# MicroMouse_v02.net
KiCad netlist of a schematic drawn in EasyEDA Pro
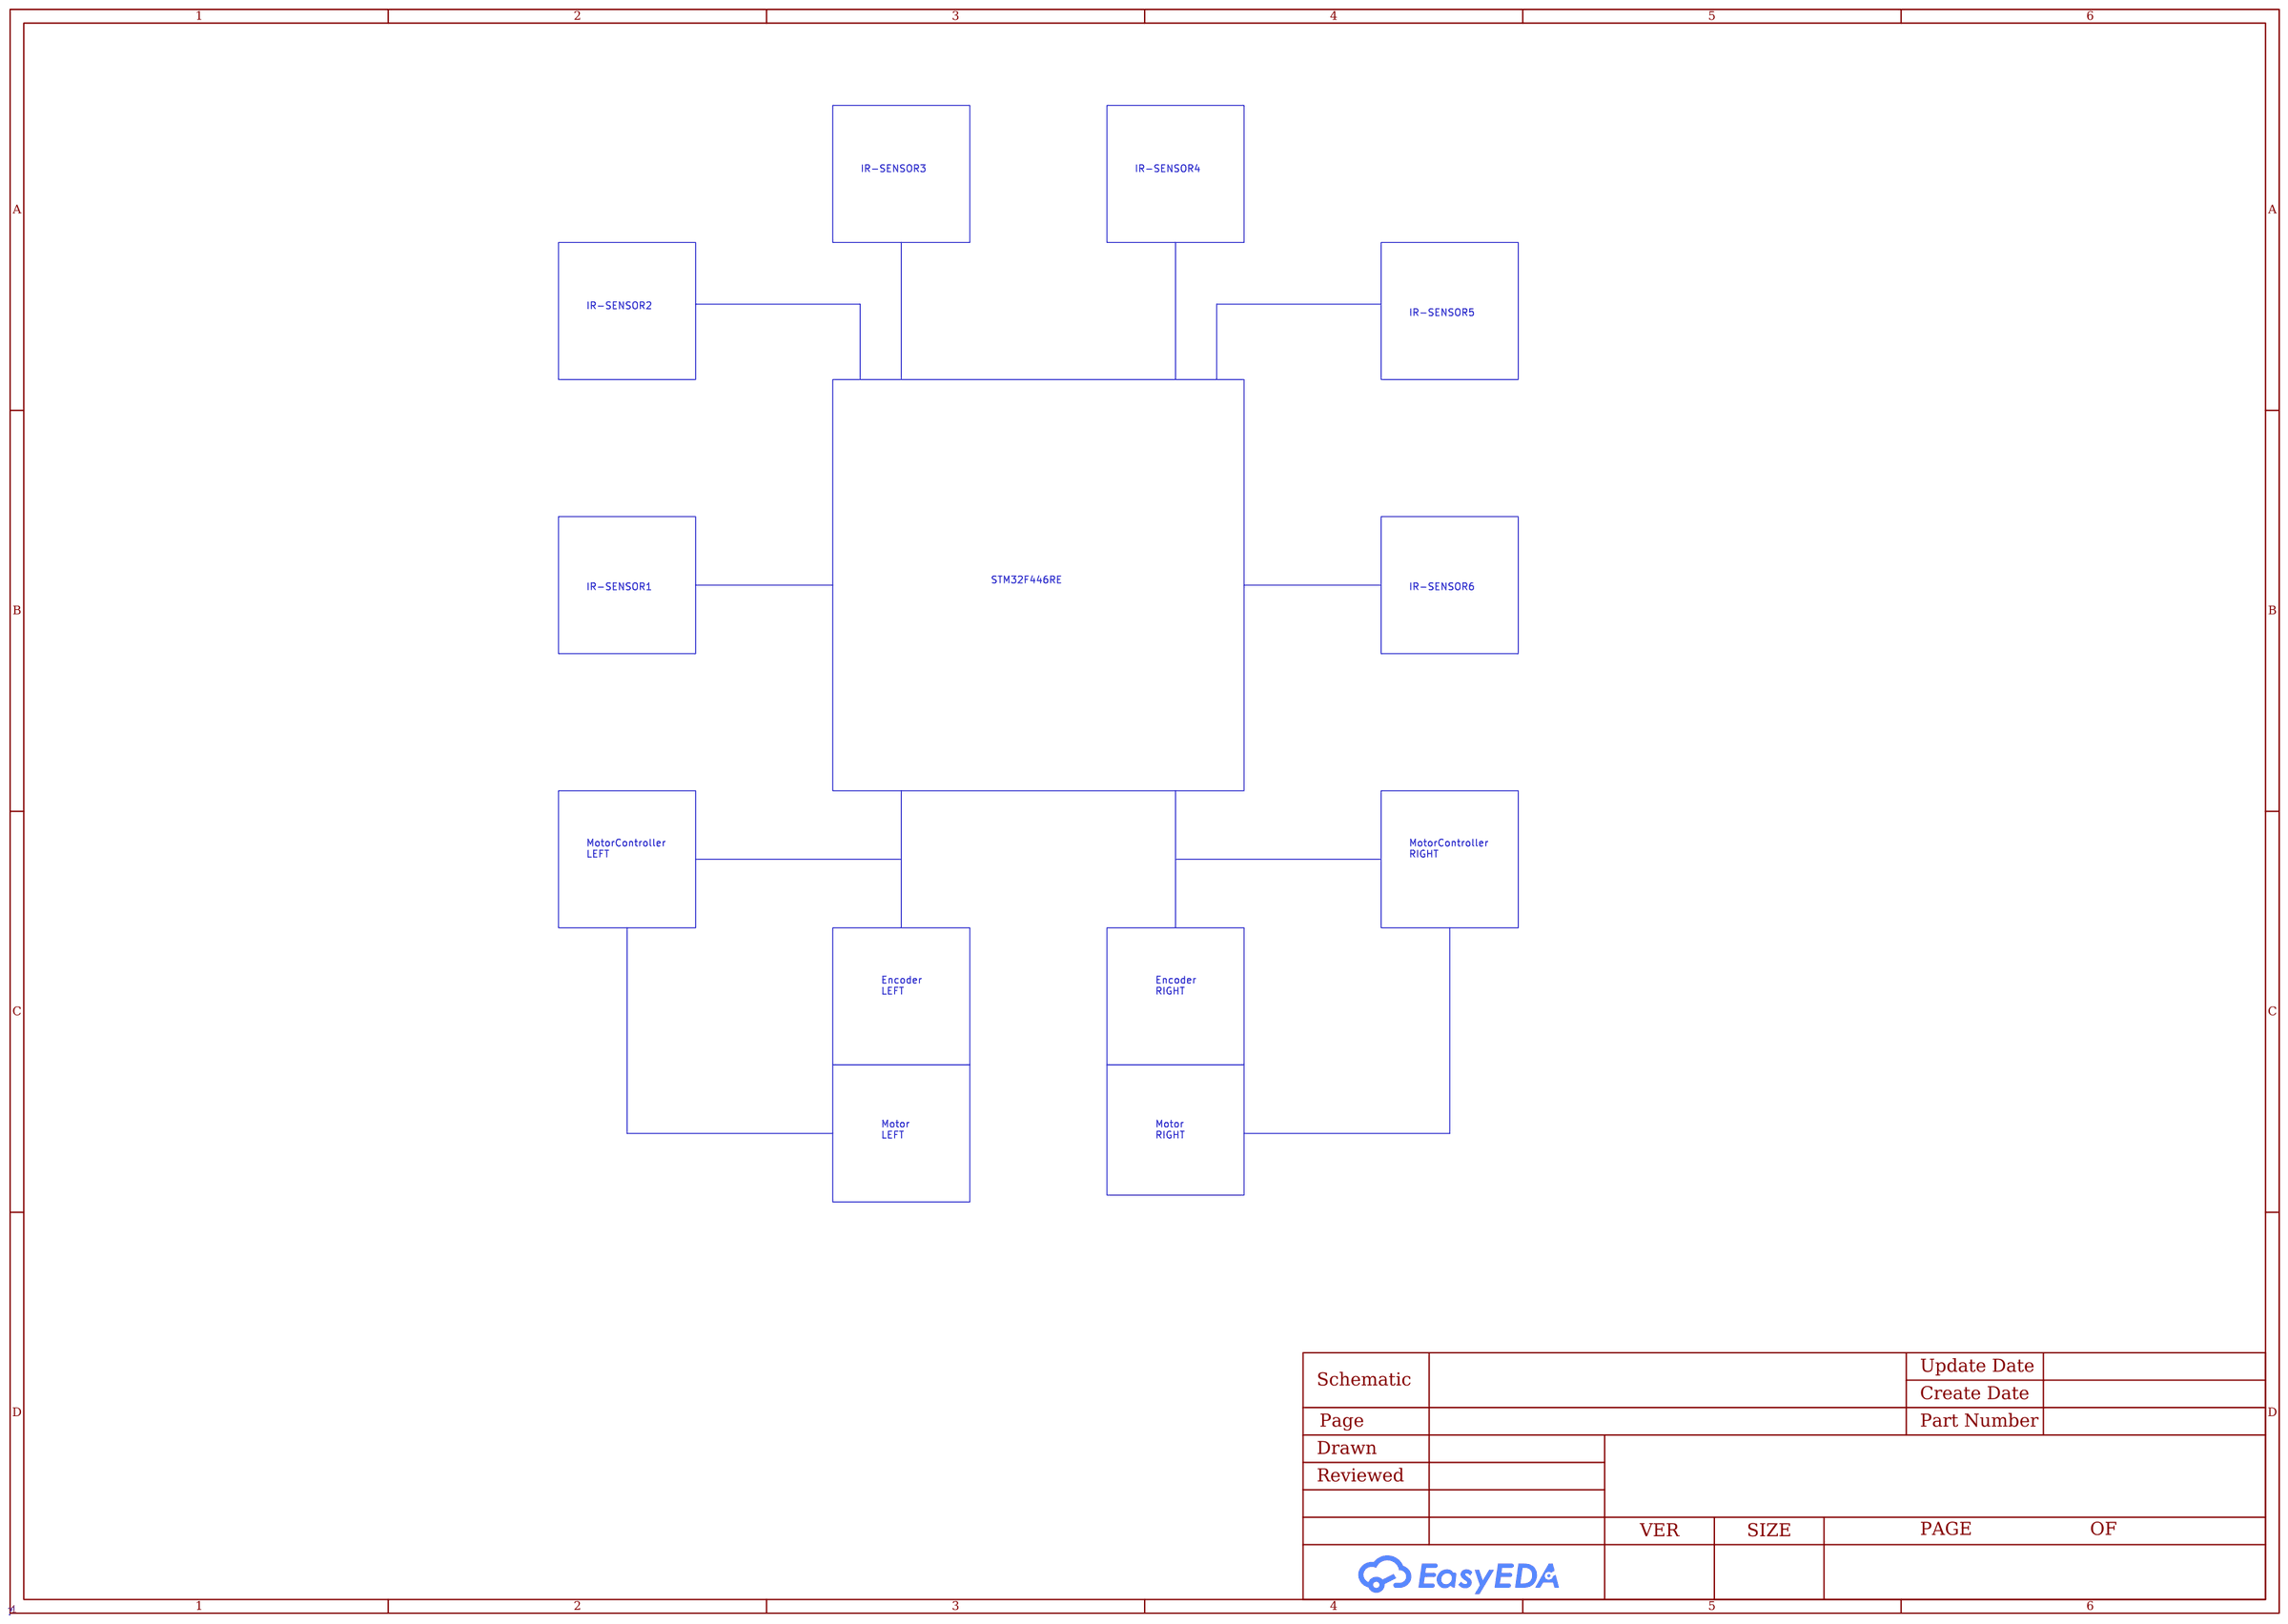
[diagram p0: Overview]
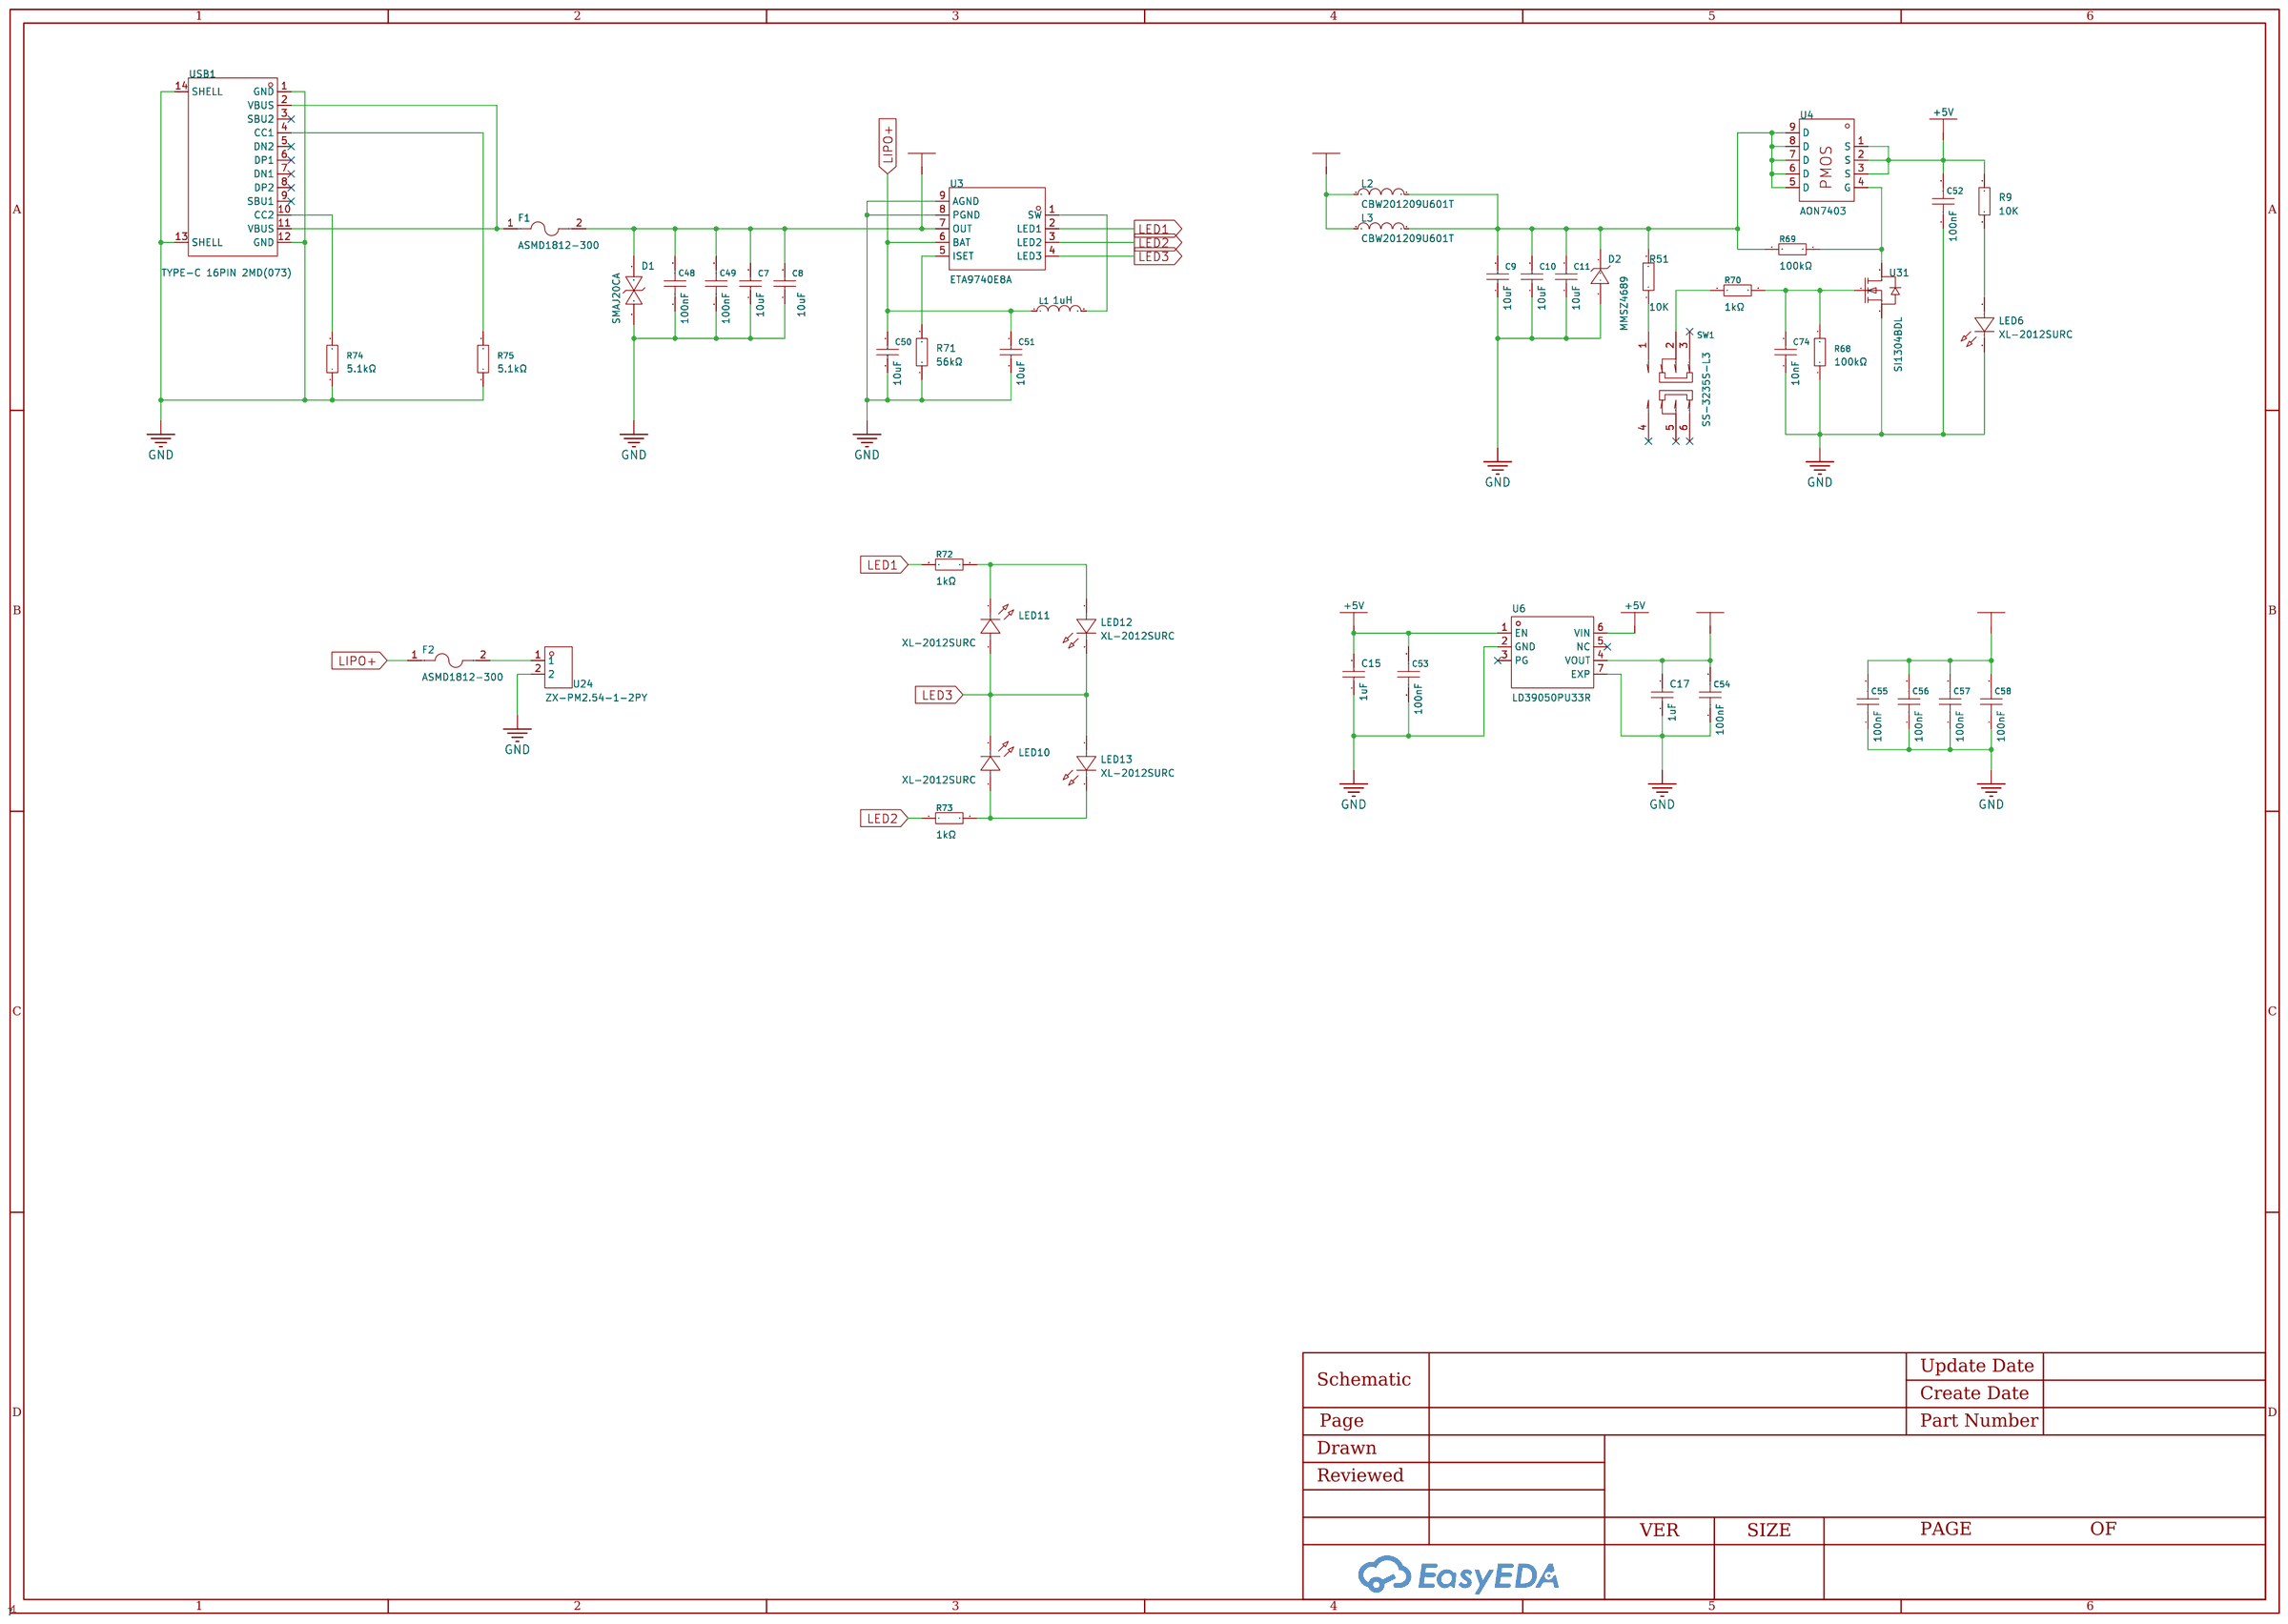
[diagram p1: VCC]
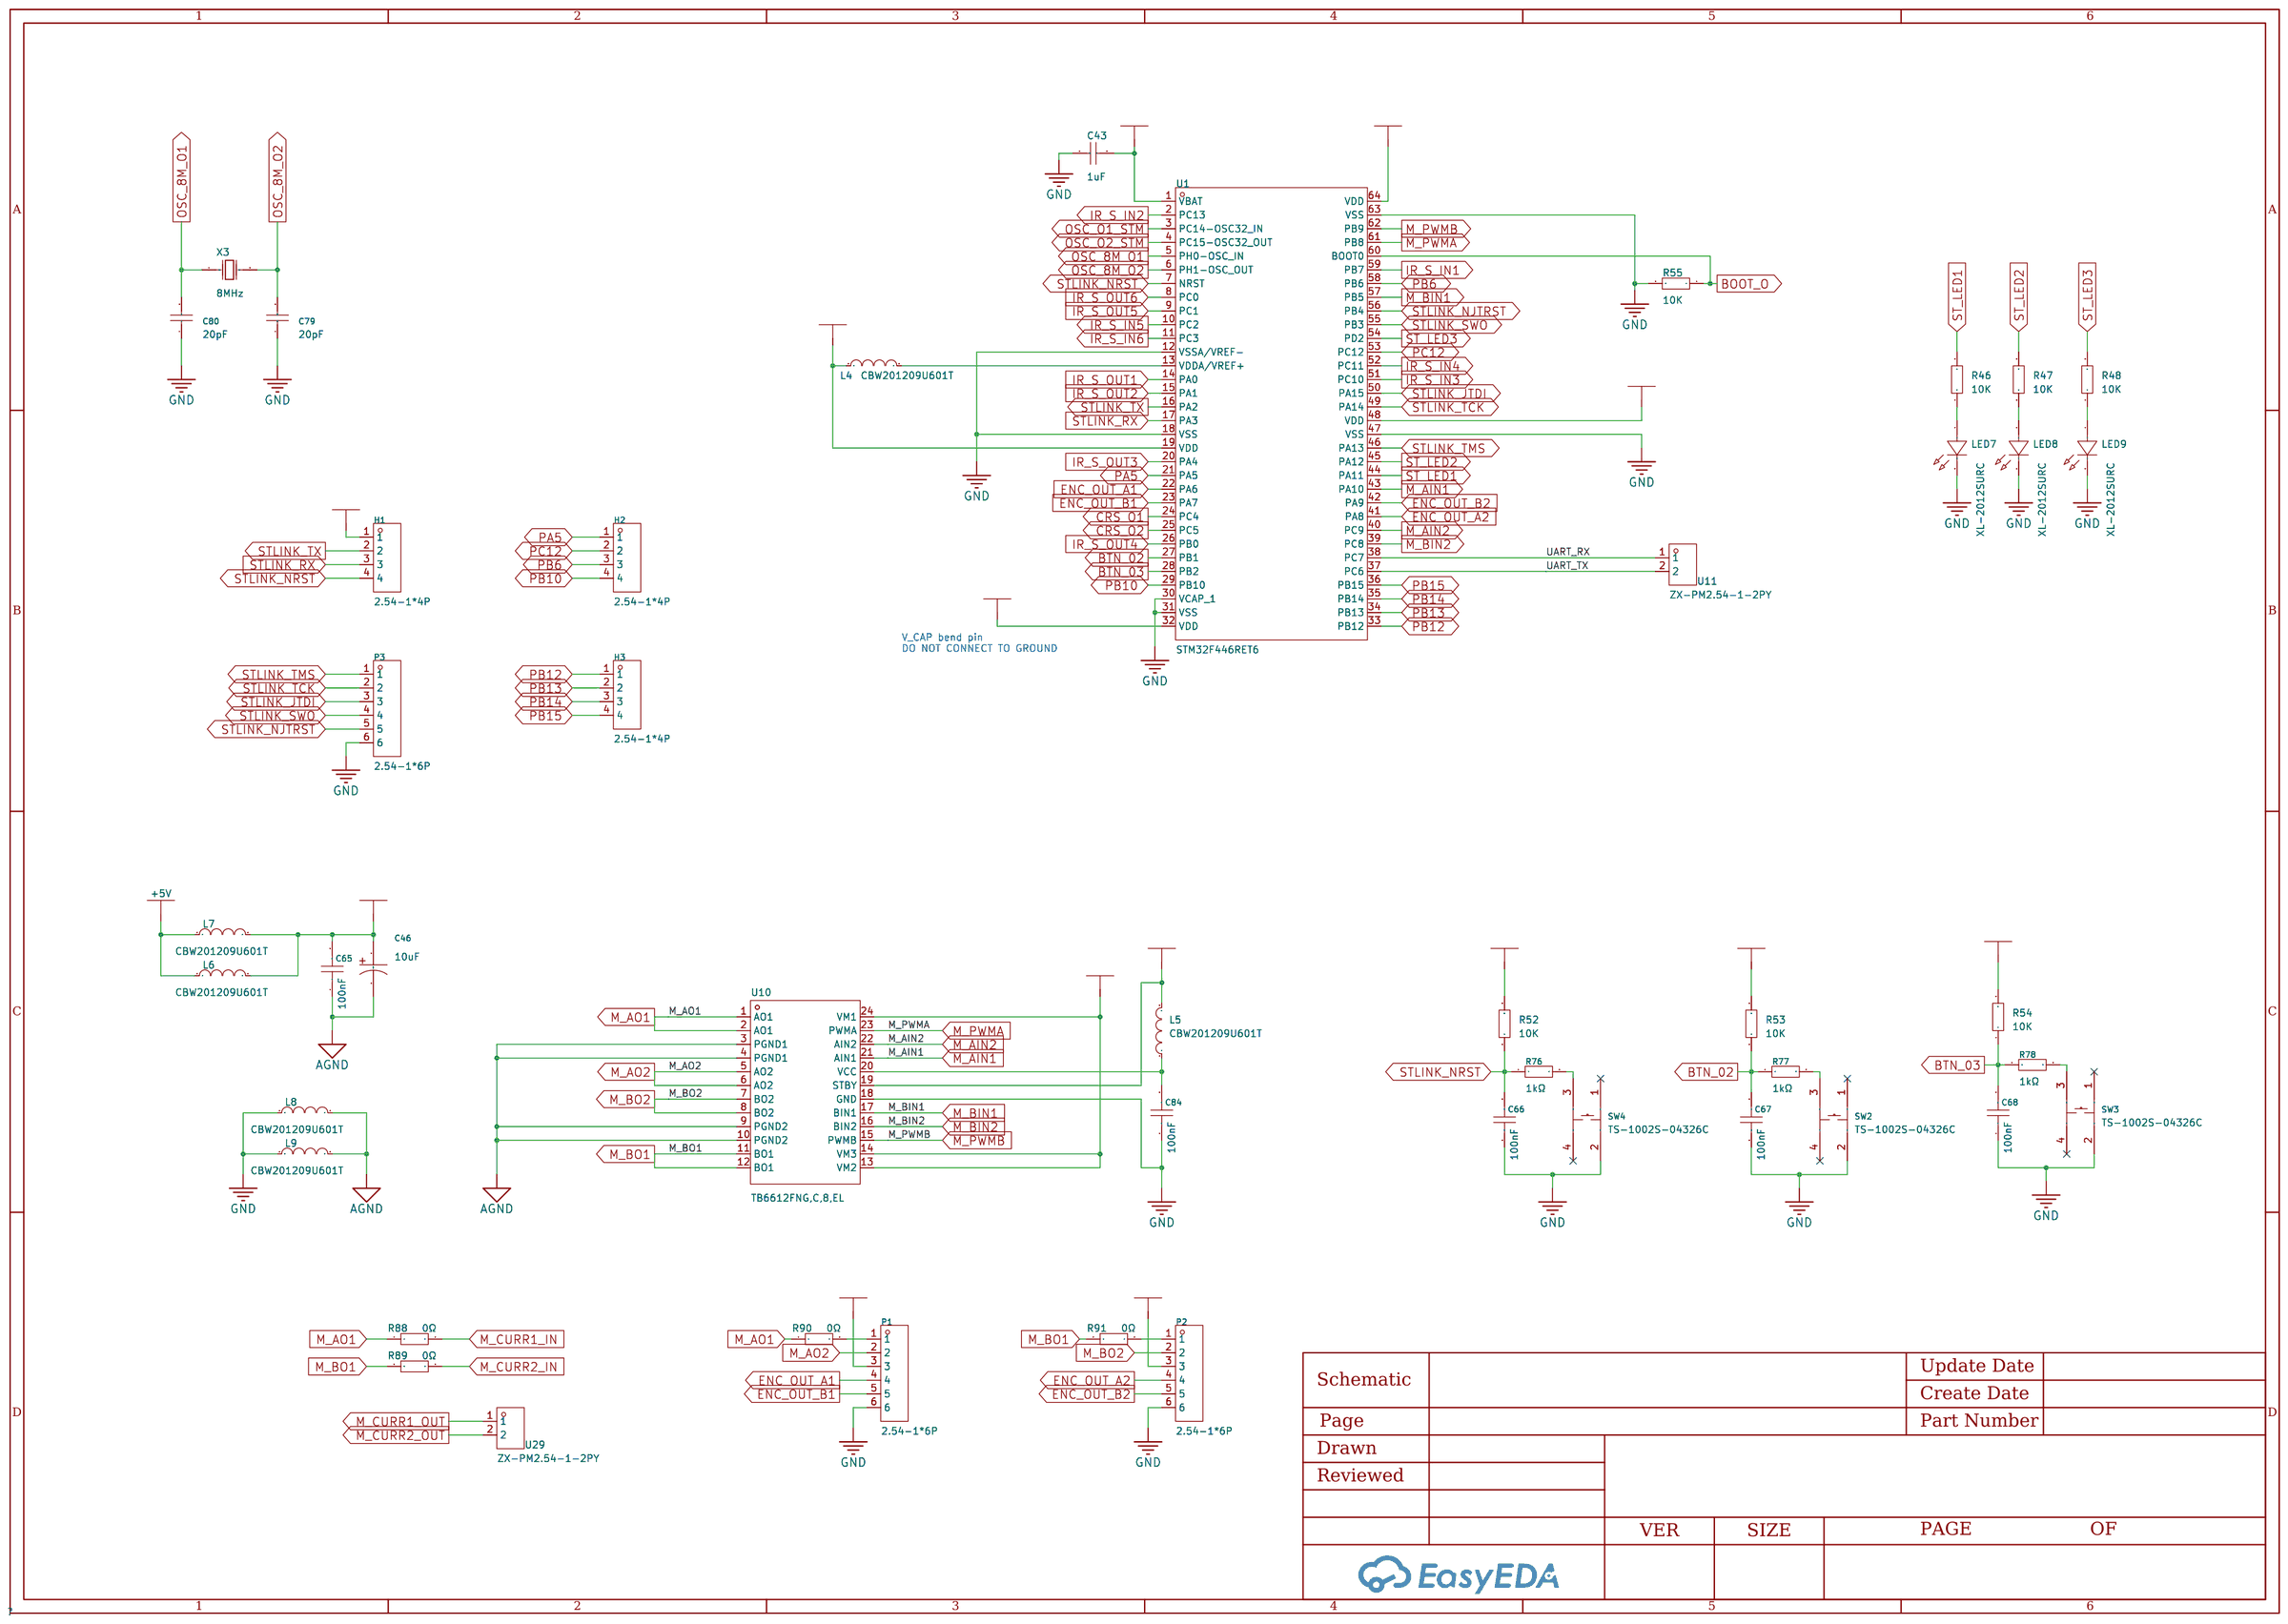
[diagram p2: Controller]
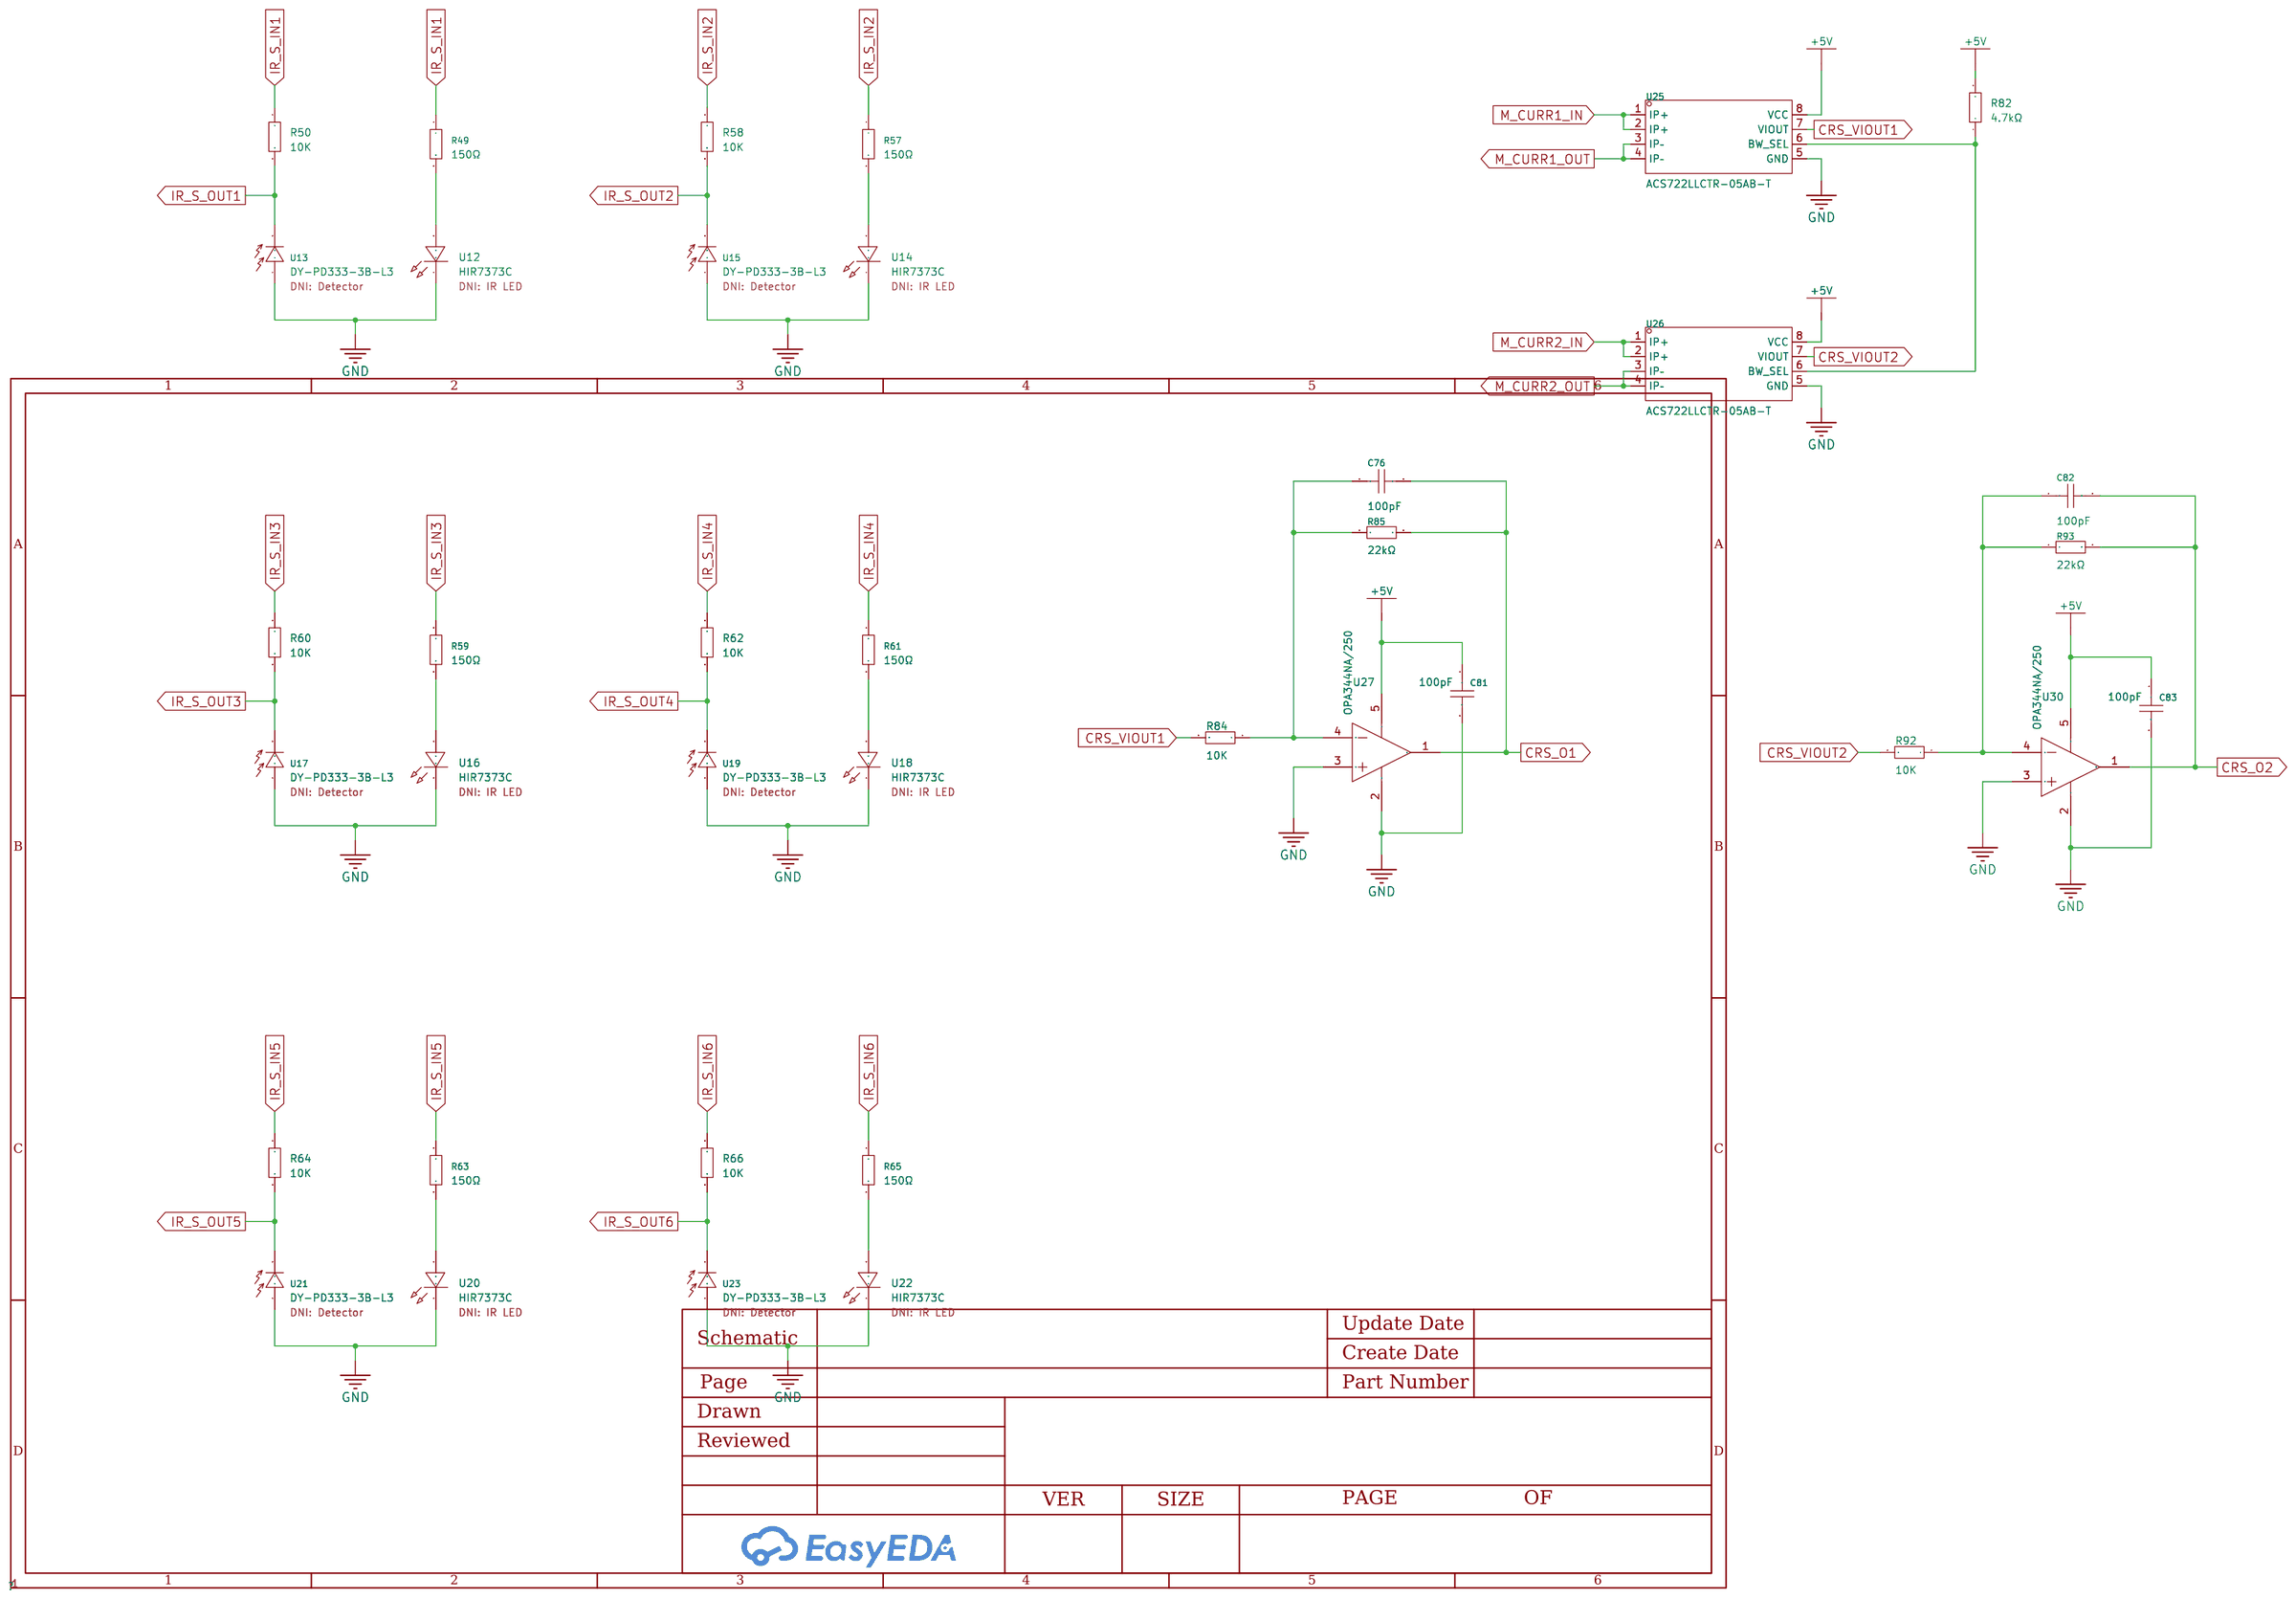
[diagram p3: Sensors]

(export (version "E")
  (design (tool "Eeschema 10.0.6"))
  (components
    (comp (ref "C7")
      (value "10uF")
      (footprint "easyedapro:C0805")
      (fields
        (field (name "Manufacturer Part") "CL21A106KPFNNNE")
        (field (name "Manufacturer") "SAMSUNG(三星)")
      )
      (libsource (lib "easyedapro") (part "CL21A106KPFNNNE"))
    )
    (comp (ref "C8")
      (value "10uF")
      (footprint "easyedapro:C0805")
      (fields
        (field (name "Manufacturer Part") "CL21A106KPFNNNE")
        (field (name "Manufacturer") "SAMSUNG(三星)")
      )
      (libsource (lib "easyedapro") (part "CL21A106KPFNNNE"))
    )
    (comp (ref "C9")
      (value "10uF")
      (footprint "easyedapro:C0805")
      (fields
        (field (name "Manufacturer Part") "CL21A106KPFNNNE")
        (field (name "Manufacturer") "SAMSUNG(三星)")
      )
      (libsource (lib "easyedapro") (part "CL21A106KPFNNNE"))
    )
    (comp (ref "C10")
      (value "10uF")
      (footprint "easyedapro:C0805")
      (fields
        (field (name "Manufacturer Part") "CL21A106KPFNNNE")
        (field (name "Manufacturer") "SAMSUNG(三星)")
      )
      (libsource (lib "easyedapro") (part "CL21A106KPFNNNE"))
    )
    (comp (ref "C11")
      (value "10uF")
      (footprint "easyedapro:C0805")
      (fields
        (field (name "Manufacturer Part") "CL21A106KPFNNNE")
        (field (name "Manufacturer") "SAMSUNG(三星)")
      )
      (libsource (lib "easyedapro") (part "CL21A106KPFNNNE"))
    )
    (comp (ref "C15")
      (value "1uF")
      (footprint "easyedapro:C0603")
      (fields
        (field (name "Manufacturer Part") "CL10A105KO8NNNC")
        (field (name "Manufacturer") "SAMSUNG(三星)")
      )
      (libsource (lib "easyedapro") (part "CL10A105KO8NNNC"))
    )
    (comp (ref "C17")
      (value "1uF")
      (footprint "easyedapro:C0603")
      (fields
        (field (name "Manufacturer Part") "CL10A105KO8NNNC")
        (field (name "Manufacturer") "SAMSUNG(三星)")
      )
      (libsource (lib "easyedapro") (part "CL10A105KO8NNNC"))
    )
    (comp (ref "C48")
      (value "100nF")
      (footprint "easyedapro:C0603")
      (fields
        (field (name "Manufacturer Part") "CC0603KRX7R6BB104")
        (field (name "Manufacturer") "YAGEO(国巨)")
      )
      (libsource (lib "easyedapro") (part "CC0603KRX7R6BB104"))
    )
    (comp (ref "C49")
      (value "100nF")
      (footprint "easyedapro:C0603")
      (fields
        (field (name "Manufacturer Part") "CC0603KRX7R6BB104")
        (field (name "Manufacturer") "YAGEO(国巨)")
      )
      (libsource (lib "easyedapro") (part "CC0603KRX7R6BB104"))
    )
    (comp (ref "C50")
      (value "10uF")
      (footprint "easyedapro:C0805")
      (fields
        (field (name "Manufacturer Part") "CL21A106KPFNNNE")
        (field (name "Manufacturer") "SAMSUNG(三星)")
      )
      (libsource (lib "easyedapro") (part "CL21A106KPFNNNE"))
    )
    (comp (ref "C51")
      (value "10uF")
      (footprint "easyedapro:C0805")
      (fields
        (field (name "Manufacturer Part") "CL21A106KPFNNNE")
        (field (name "Manufacturer") "SAMSUNG(三星)")
      )
      (libsource (lib "easyedapro") (part "CL21A106KPFNNNE"))
    )
    (comp (ref "C52")
      (value "100nF")
      (footprint "easyedapro:C0603")
      (fields
        (field (name "Manufacturer Part") "CC0603KRX7R6BB104")
        (field (name "Manufacturer") "YAGEO(国巨)")
      )
      (libsource (lib "easyedapro") (part "CC0603KRX7R6BB104"))
    )
    (comp (ref "C53")
      (value "100nF")
      (footprint "easyedapro:C0603")
      (fields
        (field (name "Manufacturer Part") "CC0603KRX7R6BB104")
        (field (name "Manufacturer") "YAGEO(国巨)")
      )
      (libsource (lib "easyedapro") (part "CC0603KRX7R6BB104"))
    )
    (comp (ref "C54")
      (value "100nF")
      (footprint "easyedapro:C0603")
      (fields
        (field (name "Manufacturer Part") "CC0603KRX7R6BB104")
        (field (name "Manufacturer") "YAGEO(国巨)")
      )
      (libsource (lib "easyedapro") (part "CC0603KRX7R6BB104"))
    )
    (comp (ref "C55")
      (value "100nF")
      (footprint "easyedapro:C0603")
      (fields
        (field (name "Manufacturer Part") "CC0603KRX7R6BB104")
        (field (name "Manufacturer") "YAGEO(国巨)")
      )
      (libsource (lib "easyedapro") (part "CC0603KRX7R6BB104"))
    )
    (comp (ref "C56")
      (value "100nF")
      (footprint "easyedapro:C0603")
      (fields
        (field (name "Manufacturer Part") "CC0603KRX7R6BB104")
        (field (name "Manufacturer") "YAGEO(国巨)")
      )
      (libsource (lib "easyedapro") (part "CC0603KRX7R6BB104"))
    )
    (comp (ref "C57")
      (value "100nF")
      (footprint "easyedapro:C0603")
      (fields
        (field (name "Manufacturer Part") "CC0603KRX7R6BB104")
        (field (name "Manufacturer") "YAGEO(国巨)")
      )
      (libsource (lib "easyedapro") (part "CC0603KRX7R6BB104"))
    )
    (comp (ref "C58")
      (value "100nF")
      (footprint "easyedapro:C0603")
      (fields
        (field (name "Manufacturer Part") "CC0603KRX7R6BB104")
        (field (name "Manufacturer") "YAGEO(国巨)")
      )
      (libsource (lib "easyedapro") (part "CC0603KRX7R6BB104"))
    )
    (comp (ref "C74")
      (value "10nF")
      (footprint "easyedapro:C0603")
      (fields
        (field (name "Manufacturer Part") "CC0603KRX7R9BB103")
        (field (name "Manufacturer") "YAGEO(国巨)")
      )
      (libsource (lib "easyedapro") (part "CC0603KRX7R9BB103"))
    )
    (comp (ref "D1")
      (value "SMAJ20CA")
      (footprint "easyedapro:SMA_L4.3-W2.6-LS5.2-BI")
      (fields (field (name "Manufacturer") "High Diode(海德)"))
      (libsource (lib "easyedapro") (part "SMAJ20CA_C514090"))
    )
    (comp (ref "D2")
      (value "MMSZ4689")
      (footprint "easyedapro:SOD-123_L2.8-W1.8-LS3.7-RD")
      (fields (field (name "Manufacturer") "CJ(江苏长电/长晶)"))
      (libsource (lib "easyedapro") (part "MMSZ4689"))
    )
    (comp (ref "F1")
      (value "ASMD1812-300")
      (footprint "easyedapro:F1812")
      (fields (field (name "Manufacturer") "JDTfuse(集电通)"))
      (libsource (lib "easyedapro") (part "ASMD1812-300"))
    )
    (comp (ref "F2")
      (value "ASMD1812-300")
      (footprint "easyedapro:F1812")
      (fields (field (name "Manufacturer") "JDTfuse(集电通)"))
      (libsource (lib "easyedapro") (part "ASMD1812-300"))
    )
    (comp (ref "L1")
      (value "1uH")
      (footprint "easyedapro:IND-SMD_L7.2-W6.6_GPSR0730")
      (fields (field (name "Manufacturer Part") "CYA0630-1.0UH") (field (name "Manufacturer") "SHOU HAN(首韩)"))
      (libsource (lib "easyedapro") (part "CYA0630-1.0UH"))
    )
    (comp (ref "L2")
      (value "CBW201209U601T")
      (footprint "easyedapro:L0805")
      (fields (field (name "Manufacturer") "FH(风华)"))
      (libsource (lib "easyedapro") (part "CBW201209U601T"))
    )
    (comp (ref "L3")
      (value "CBW201209U601T")
      (footprint "easyedapro:L0805")
      (fields (field (name "Manufacturer") "FH(风华)"))
      (libsource (lib "easyedapro") (part "CBW201209U601T"))
    )
    (comp (ref "LED6")
      (value "XL-2012SURC")
      (footprint "easyedapro:LED0805-R-RD")
      (fields (field (name "Manufacturer") "XINGLIGHT(成兴光)"))
      (libsource (lib "easyedapro") (part "XL-2012SURC"))
    )
    (comp (ref "LED10")
      (value "XL-2012SURC")
      (footprint "easyedapro:LED0805-R-RD")
      (fields (field (name "Manufacturer") "XINGLIGHT(成兴光)"))
      (libsource (lib "easyedapro") (part "XL-2012SURC"))
    )
    (comp (ref "LED11")
      (value "XL-2012SURC")
      (footprint "easyedapro:LED0805-R-RD")
      (fields (field (name "Manufacturer") "XINGLIGHT(成兴光)"))
      (libsource (lib "easyedapro") (part "XL-2012SURC"))
    )
    (comp (ref "LED12")
      (value "XL-2012SURC")
      (footprint "easyedapro:LED0805-R-RD")
      (fields (field (name "Manufacturer") "XINGLIGHT(成兴光)"))
      (libsource (lib "easyedapro") (part "XL-2012SURC"))
    )
    (comp (ref "LED13")
      (value "XL-2012SURC")
      (footprint "easyedapro:LED0805-R-RD")
      (fields (field (name "Manufacturer") "XINGLIGHT(成兴光)"))
      (libsource (lib "easyedapro") (part "XL-2012SURC"))
    )
    (comp (ref "R9")
      (value "10K")
      (footprint "easyedapro:R0603")
      (description "DNI")
      (libsource (lib "easyedapro") (part "Res"))
    )
    (comp (ref "R51")
      (value "10K")
      (footprint "easyedapro:R0603")
      (description "DNI")
      (libsource (lib "easyedapro") (part "Res"))
    )
    (comp (ref "R68")
      (value "100kΩ")
      (footprint "easyedapro:R0603")
      (fields (field (name "Manufacturer Part") "RC0603FR-07100KL") (field (name "Manufacturer") "YAGEO(国巨)"))
      (libsource (lib "easyedapro") (part "RC0603FR-07100KL"))
    )
    (comp (ref "R69")
      (value "100kΩ")
      (footprint "easyedapro:R0603")
      (fields (field (name "Manufacturer Part") "RC0603FR-07100KL") (field (name "Manufacturer") "YAGEO(国巨)"))
      (libsource (lib "easyedapro") (part "RC0603FR-07100KL"))
    )
    (comp (ref "R70")
      (value "1kΩ")
      (footprint "easyedapro:R0603")
      (fields
        (field (name "Manufacturer Part") "0603WAF1001T5E")
        (field (name "Manufacturer") "UNI-ROYAL(厚声)")
      )
      (libsource (lib "easyedapro") (part "0603WAF1001T5E"))
    )
    (comp (ref "R71")
      (value "56kΩ")
      (footprint "easyedapro:R0603")
      (fields (field (name "Manufacturer Part") "RC0603FR-0756KL") (field (name "Manufacturer") "YAGEO(国巨)"))
      (libsource (lib "easyedapro") (part "RC0603FR-0756KL"))
    )
    (comp (ref "R72")
      (value "1kΩ")
      (footprint "easyedapro:R0603")
      (fields
        (field (name "Manufacturer Part") "0603WAF1001T5E")
        (field (name "Manufacturer") "UNI-ROYAL(厚声)")
      )
      (libsource (lib "easyedapro") (part "0603WAF1001T5E"))
    )
    (comp (ref "R73")
      (value "1kΩ")
      (footprint "easyedapro:R0603")
      (fields
        (field (name "Manufacturer Part") "0603WAF1001T5E")
        (field (name "Manufacturer") "UNI-ROYAL(厚声)")
      )
      (libsource (lib "easyedapro") (part "0603WAF1001T5E"))
    )
    (comp (ref "R74")
      (value "5.1kΩ")
      (footprint "easyedapro:R0603")
      (fields
        (field (name "Manufacturer Part") "0603WAF5101T5E")
        (field (name "Manufacturer") "UNI-ROYAL(厚声)")
      )
      (libsource (lib "easyedapro") (part "0603WAF5101T5E"))
    )
    (comp (ref "R75")
      (value "5.1kΩ")
      (footprint "easyedapro:R0603")
      (fields
        (field (name "Manufacturer Part") "0603WAF5101T5E")
        (field (name "Manufacturer") "UNI-ROYAL(厚声)")
      )
      (libsource (lib "easyedapro") (part "0603WAF5101T5E"))
    )
    (comp (ref "SW1")
      (value "SS-3235S-L3")
      (footprint "easyedapro:SW-SMD_SS-3235S-L3.00")
      (fields (field (name "Manufacturer") "XKB Connectivity(中国星坤)"))
      (libsource (lib "easyedapro") (part "SS-3235S-L3"))
    )
    (comp (ref "U3")
      (value "ETA9740E8A")
      (footprint "easyedapro:ESOP-8_L4.9-W3.9-P1.27-LS6.0-BL-EP-1")
      (fields (field (name "Manufacturer") "ETA(钰泰）"))
      (libsource (lib "easyedapro") (part "ETA9740E8A"))
    )
    (comp (ref "U4")
      (value "AON7403")
      (footprint "easyedapro:DFN-8_L3.0-W3.0-P0.65-BL")
      (fields (field (name "Manufacturer") "TECH PUBLIC(台舟)"))
      (libsource (lib "easyedapro") (part "AON7403_C5310961"))
    )
    (comp (ref "U6")
      (value "LD39050PU33R")
      (footprint "easyedapro:DFN-6_L3.0-W3.0-P0.95-LS3.1-TL-EP")
      (fields (field (name "Manufacturer") "ST(意法半导体)"))
      (libsource (lib "easyedapro") (part "LD39050PU33R"))
    )
    (comp (ref "U24")
      (value "ZX-PM2.54-1-2PY")
      (footprint "easyedapro:HDR-TH_2P-P2.54-V-F")
      (fields (field (name "Manufacturer") "Megastar(兆星)"))
      (libsource (lib "easyedapro") (part "ZX-PM2.54-1-2PY"))
    )
    (comp (ref "U31")
      (value "SI1304BDL")
      (footprint "easyedapro:SOT-323-3_L2.0-W1.3-P1.30-LS2.1-BL")
      (fields (field (name "Manufacturer") "TECH PUBLIC(台舟)"))
      (libsource (lib "easyedapro") (part "SI1304BDL_C7419947"))
    )
    (comp (ref "USB1")
      (value "TYPE-C 16PIN 2MD(073)")
      (footprint "easyedapro:USB-C-SMD_TYPE-C-6PIN-2MD-073")
      (fields (field (name "Manufacturer") "SHOU HAN(首韩)"))
      (libsource (lib "easyedapro") (part "TYPE-C 16PIN 2MD(073)"))
    )
    (comp (ref "C43")
      (value "1uF")
      (footprint "easyedapro:C0603")
      (fields
        (field (name "Manufacturer Part") "CL10A105KO8NNNC")
        (field (name "Manufacturer") "SAMSUNG(三星)")
      )
      (libsource (lib "easyedapro") (part "CL10A105KO8NNNC"))
    )
    (comp (ref "C46")
      (value "10uF")
      (footprint "easyedapro:CAP-TH_BD5.0-P5.00-D1.0-FD")
      (fields
        (field (name "Manufacturer Part") "UVZ1C100MDD1TA")
        (field (name "Manufacturer") "Nichicon(尼吉康)")
      )
      (libsource (lib "easyedapro") (part "UVZ1C100MDD1TA"))
    )
    (comp (ref "C65")
      (value "100nF")
      (footprint "easyedapro:C0603")
      (fields
        (field (name "Manufacturer Part") "CC0603KRX7R6BB104")
        (field (name "Manufacturer") "YAGEO(国巨)")
      )
      (libsource (lib "easyedapro") (part "CC0603KRX7R6BB104"))
    )
    (comp (ref "C66")
      (value "100nF")
      (footprint "easyedapro:C0603")
      (fields
        (field (name "Manufacturer Part") "CC0603KRX7R6BB104")
        (field (name "Manufacturer") "YAGEO(国巨)")
      )
      (libsource (lib "easyedapro") (part "CC0603KRX7R6BB104"))
    )
    (comp (ref "C67")
      (value "100nF")
      (footprint "easyedapro:C0603")
      (fields
        (field (name "Manufacturer Part") "CC0603KRX7R6BB104")
        (field (name "Manufacturer") "YAGEO(国巨)")
      )
      (libsource (lib "easyedapro") (part "CC0603KRX7R6BB104"))
    )
    (comp (ref "C68")
      (value "100nF")
      (footprint "easyedapro:C0603")
      (fields
        (field (name "Manufacturer Part") "CC0603KRX7R6BB104")
        (field (name "Manufacturer") "YAGEO(国巨)")
      )
      (libsource (lib "easyedapro") (part "CC0603KRX7R6BB104"))
    )
    (comp (ref "C79")
      (value "20pF")
      (footprint "easyedapro:C0603")
      (fields
        (field (name "Manufacturer Part") "CC0603JRNPO9BN200")
        (field (name "Manufacturer") "YAGEO(国巨)")
      )
      (libsource (lib "easyedapro") (part "CC0603JRNPO9BN200"))
    )
    (comp (ref "C80")
      (value "20pF")
      (footprint "easyedapro:C0603")
      (fields
        (field (name "Manufacturer Part") "CC0603JRNPO9BN200")
        (field (name "Manufacturer") "YAGEO(国巨)")
      )
      (libsource (lib "easyedapro") (part "CC0603JRNPO9BN200"))
    )
    (comp (ref "C84")
      (value "100nF")
      (footprint "easyedapro:C0603")
      (fields
        (field (name "Manufacturer Part") "CC0603KRX7R6BB104")
        (field (name "Manufacturer") "YAGEO(国巨)")
      )
      (libsource (lib "easyedapro") (part "CC0603KRX7R6BB104"))
    )
    (comp (ref "H1")
      (value "2.54-1*4P")
      (footprint "easyedapro:HDR-TH_4P-P2.54-V-F")
      (fields (field (name "Manufacturer") "BOOMELE(博穆精密)"))
      (libsource (lib "easyedapro") (part "2.54-1*4P母"))
    )
    (comp (ref "H2")
      (value "2.54-1*4P")
      (footprint "easyedapro:HDR-TH_4P-P2.54-V-F")
      (fields (field (name "Manufacturer") "BOOMELE(博穆精密)"))
      (libsource (lib "easyedapro") (part "2.54-1*4P母"))
    )
    (comp (ref "H3")
      (value "2.54-1*4P")
      (footprint "easyedapro:HDR-TH_4P-P2.54-V-F")
      (fields (field (name "Manufacturer") "BOOMELE(博穆精密)"))
      (libsource (lib "easyedapro") (part "2.54-1*4P母"))
    )
    (comp (ref "L4")
      (value "CBW201209U601T")
      (footprint "easyedapro:L0805")
      (fields (field (name "Manufacturer") "FH(风华)"))
      (libsource (lib "easyedapro") (part "CBW201209U601T"))
    )
    (comp (ref "L5")
      (value "CBW201209U601T")
      (footprint "easyedapro:L0805")
      (fields (field (name "Manufacturer") "FH(风华)"))
      (libsource (lib "easyedapro") (part "CBW201209U601T"))
    )
    (comp (ref "L6")
      (value "CBW201209U601T")
      (footprint "easyedapro:L0805")
      (fields (field (name "Manufacturer") "FH(风华)"))
      (libsource (lib "easyedapro") (part "CBW201209U601T"))
    )
    (comp (ref "L7")
      (value "CBW201209U601T")
      (footprint "easyedapro:L0805")
      (fields (field (name "Manufacturer") "FH(风华)"))
      (libsource (lib "easyedapro") (part "CBW201209U601T"))
    )
    (comp (ref "L8")
      (value "CBW201209U601T")
      (footprint "easyedapro:L0805")
      (fields (field (name "Manufacturer") "FH(风华)"))
      (libsource (lib "easyedapro") (part "CBW201209U601T"))
    )
    (comp (ref "L9")
      (value "CBW201209U601T")
      (footprint "easyedapro:L0805")
      (fields (field (name "Manufacturer") "FH(风华)"))
      (libsource (lib "easyedapro") (part "CBW201209U601T"))
    )
    (comp (ref "LED7")
      (value "XL-2012SURC")
      (footprint "easyedapro:LED0805-R-RD")
      (fields (field (name "Manufacturer") "XINGLIGHT(成兴光)"))
      (libsource (lib "easyedapro") (part "XL-2012SURC"))
    )
    (comp (ref "LED8")
      (value "XL-2012SURC")
      (footprint "easyedapro:LED0805-R-RD")
      (fields (field (name "Manufacturer") "XINGLIGHT(成兴光)"))
      (libsource (lib "easyedapro") (part "XL-2012SURC"))
    )
    (comp (ref "LED9")
      (value "XL-2012SURC")
      (footprint "easyedapro:LED0805-R-RD")
      (fields (field (name "Manufacturer") "XINGLIGHT(成兴光)"))
      (libsource (lib "easyedapro") (part "XL-2012SURC"))
    )
    (comp (ref "P1")
      (value "2.54-1*6P")
      (footprint "easyedapro:HDR-TH_6P-P2.54-V-F")
      (fields (field (name "Manufacturer") "BOOMELE(博穆精密)"))
      (libsource (lib "easyedapro") (part "Header-Female-2.54_1x6"))
    )
    (comp (ref "P2")
      (value "2.54-1*6P")
      (footprint "easyedapro:HDR-TH_6P-P2.54-V-F")
      (fields (field (name "Manufacturer") "BOOMELE(博穆精密)"))
      (libsource (lib "easyedapro") (part "Header-Female-2.54_1x6"))
    )
    (comp (ref "P3")
      (value "2.54-1*6P")
      (footprint "easyedapro:HDR-TH_6P-P2.54-V-F")
      (fields (field (name "Manufacturer") "BOOMELE(博穆精密)"))
      (libsource (lib "easyedapro") (part "Header-Female-2.54_1x6"))
    )
    (comp (ref "R46")
      (value "10K")
      (footprint "easyedapro:R0603")
      (description "DNI")
      (libsource (lib "easyedapro") (part "Res"))
    )
    (comp (ref "R47")
      (value "10K")
      (footprint "easyedapro:R0603")
      (description "DNI")
      (libsource (lib "easyedapro") (part "Res"))
    )
    (comp (ref "R48")
      (value "10K")
      (footprint "easyedapro:R0603")
      (description "DNI")
      (libsource (lib "easyedapro") (part "Res"))
    )
    (comp (ref "R52")
      (value "10K")
      (footprint "easyedapro:R0603")
      (description "DNI")
      (libsource (lib "easyedapro") (part "Res"))
    )
    (comp (ref "R53")
      (value "10K")
      (footprint "easyedapro:R0603")
      (description "DNI")
      (libsource (lib "easyedapro") (part "Res"))
    )
    (comp (ref "R54")
      (value "10K")
      (footprint "easyedapro:R0603")
      (description "DNI")
      (libsource (lib "easyedapro") (part "Res"))
    )
    (comp (ref "R55")
      (value "10K")
      (footprint "easyedapro:R0603")
      (description "DNI")
      (libsource (lib "easyedapro") (part "Res"))
    )
    (comp (ref "R76")
      (value "1kΩ")
      (footprint "easyedapro:R0603")
      (fields
        (field (name "Manufacturer Part") "0603WAF1001T5E")
        (field (name "Manufacturer") "UNI-ROYAL(厚声)")
      )
      (libsource (lib "easyedapro") (part "0603WAF1001T5E"))
    )
    (comp (ref "R77")
      (value "1kΩ")
      (footprint "easyedapro:R0603")
      (fields
        (field (name "Manufacturer Part") "0603WAF1001T5E")
        (field (name "Manufacturer") "UNI-ROYAL(厚声)")
      )
      (libsource (lib "easyedapro") (part "0603WAF1001T5E"))
    )
    (comp (ref "R78")
      (value "1kΩ")
      (footprint "easyedapro:R0603")
      (fields
        (field (name "Manufacturer Part") "0603WAF1001T5E")
        (field (name "Manufacturer") "UNI-ROYAL(厚声)")
      )
      (libsource (lib "easyedapro") (part "0603WAF1001T5E"))
    )
    (comp (ref "R88")
      (value "0Ω")
      (footprint "easyedapro:R0603")
      (fields
        (field (name "Manufacturer Part") "0603WAF0000T5E")
        (field (name "Manufacturer") "UNI-ROYAL(厚声)")
      )
      (libsource (lib "easyedapro") (part "0603WAF0000T5E"))
    )
    (comp (ref "R89")
      (value "0Ω")
      (footprint "easyedapro:R0603")
      (fields
        (field (name "Manufacturer Part") "0603WAF0000T5E")
        (field (name "Manufacturer") "UNI-ROYAL(厚声)")
      )
      (libsource (lib "easyedapro") (part "0603WAF0000T5E"))
    )
    (comp (ref "R90")
      (value "0Ω")
      (footprint "easyedapro:R0603")
      (fields
        (field (name "Manufacturer Part") "0603WAF0000T5E")
        (field (name "Manufacturer") "UNI-ROYAL(厚声)")
      )
      (libsource (lib "easyedapro") (part "0603WAF0000T5E"))
    )
    (comp (ref "R91")
      (value "0Ω")
      (footprint "easyedapro:R0603")
      (fields
        (field (name "Manufacturer Part") "0603WAF0000T5E")
        (field (name "Manufacturer") "UNI-ROYAL(厚声)")
      )
      (libsource (lib "easyedapro") (part "0603WAF0000T5E"))
    )
    (comp (ref "SW2")
      (value "TS-1002S-04326C")
      (footprint "easyedapro:KEY-SMD_4P-L6.0-W6.0-P4.50-LS9.0")
      (fields (field (name "Manufacturer") "XUNPU(讯普)"))
      (libsource (lib "easyedapro") (part "TS-1002S-04326C"))
    )
    (comp (ref "SW3")
      (value "TS-1002S-04326C")
      (footprint "easyedapro:KEY-SMD_4P-L6.0-W6.0-P4.50-LS9.0")
      (fields (field (name "Manufacturer") "XUNPU(讯普)"))
      (libsource (lib "easyedapro") (part "TS-1002S-04326C"))
    )
    (comp (ref "SW4")
      (value "TS-1002S-04326C")
      (footprint "easyedapro:KEY-SMD_4P-L6.0-W6.0-P4.50-LS9.0")
      (fields (field (name "Manufacturer") "XUNPU(讯普)"))
      (libsource (lib "easyedapro") (part "TS-1002S-04326C"))
    )
    (comp (ref "U1")
      (value "STM32F446RET6")
      (footprint "easyedapro:LQFP-64_L10.0-W10.0-P0.50-LS12.0-BL")
      (fields (field (name "Manufacturer") "ST(意法半导体)"))
      (libsource (lib "easyedapro") (part "STM32F446RET6"))
    )
    (comp (ref "U10")
      (value "TB6612FNG,C,8,EL")
      (footprint "easyedapro:SSOP-24_L8.3-W5.6-P0.65-LS7.6-BL")
      (fields (field (name "Manufacturer") "TOSHIBA(东芝)"))
      (libsource (lib "easyedapro") (part "TB6612FNG,C,8,EL"))
    )
    (comp (ref "U11")
      (value "ZX-PM2.54-1-2PY")
      (footprint "easyedapro:HDR-TH_2P-P2.54-V-F")
      (fields (field (name "Manufacturer") "Megastar(兆星)"))
      (libsource (lib "easyedapro") (part "ZX-PM2.54-1-2PY"))
    )
    (comp (ref "U29")
      (value "ZX-PM2.54-1-2PY")
      (footprint "easyedapro:HDR-TH_2P-P2.54-V-F")
      (fields (field (name "Manufacturer") "Megastar(兆星)"))
      (libsource (lib "easyedapro") (part "ZX-PM2.54-1-2PY"))
    )
    (comp (ref "X3")
      (value "8MHz")
      (footprint "easyedapro:CRYSTAL-SMD_L11.5-W4.8-LS12.7")
      (fields (field (name "Manufacturer Part") "X49SM8MSD2SC") (field (name "Manufacturer") "YXC(扬兴晶振)"))
      (libsource (lib "easyedapro") (part "X49SM8MSD2SC"))
    )
    (comp (ref "C76")
      (value "100pF")
      (footprint "easyedapro:C0603")
      (fields
        (field (name "Manufacturer Part") "CC0603JRNPO9BN101")
        (field (name "Manufacturer") "YAGEO(国巨)")
      )
      (libsource (lib "easyedapro") (part "CC0603JRNPO9BN101"))
    )
    (comp (ref "C81")
      (value "100pF")
      (footprint "easyedapro:C0603")
      (fields
        (field (name "Manufacturer Part") "CC0603JRNPO9BN101")
        (field (name "Manufacturer") "YAGEO(国巨)")
      )
      (libsource (lib "easyedapro") (part "CC0603JRNPO9BN101"))
    )
    (comp (ref "C82")
      (value "100pF")
      (footprint "easyedapro:C0603")
      (fields
        (field (name "Manufacturer Part") "CC0603JRNPO9BN101")
        (field (name "Manufacturer") "YAGEO(国巨)")
      )
      (libsource (lib "easyedapro") (part "CC0603JRNPO9BN101"))
    )
    (comp (ref "C83")
      (value "100pF")
      (footprint "easyedapro:C0603")
      (fields
        (field (name "Manufacturer Part") "CC0603JRNPO9BN101")
        (field (name "Manufacturer") "YAGEO(国巨)")
      )
      (libsource (lib "easyedapro") (part "CC0603JRNPO9BN101"))
    )
    (comp (ref "R49")
      (value "150Ω")
      (footprint "easyedapro:R0603")
      (fields
        (field (name "Manufacturer Part") "0603WAF1500T5E")
        (field (name "Manufacturer") "UNI-ROYAL(厚声)")
      )
      (libsource (lib "easyedapro") (part "0603WAF1500T5E"))
    )
    (comp (ref "R50")
      (value "10K")
      (footprint "easyedapro:R0603")
      (description "DNI")
      (libsource (lib "easyedapro") (part "Res"))
    )
    (comp (ref "R57")
      (value "150Ω")
      (footprint "easyedapro:R0603")
      (fields
        (field (name "Manufacturer Part") "0603WAF1500T5E")
        (field (name "Manufacturer") "UNI-ROYAL(厚声)")
      )
      (libsource (lib "easyedapro") (part "0603WAF1500T5E"))
    )
    (comp (ref "R58")
      (value "10K")
      (footprint "easyedapro:R0603")
      (description "DNI")
      (libsource (lib "easyedapro") (part "Res"))
    )
    (comp (ref "R59")
      (value "150Ω")
      (footprint "easyedapro:R0603")
      (fields
        (field (name "Manufacturer Part") "0603WAF1500T5E")
        (field (name "Manufacturer") "UNI-ROYAL(厚声)")
      )
      (libsource (lib "easyedapro") (part "0603WAF1500T5E"))
    )
    (comp (ref "R60")
      (value "10K")
      (footprint "easyedapro:R0603")
      (description "DNI")
      (libsource (lib "easyedapro") (part "Res"))
    )
    (comp (ref "R61")
      (value "150Ω")
      (footprint "easyedapro:R0603")
      (fields
        (field (name "Manufacturer Part") "0603WAF1500T5E")
        (field (name "Manufacturer") "UNI-ROYAL(厚声)")
      )
      (libsource (lib "easyedapro") (part "0603WAF1500T5E"))
    )
    (comp (ref "R62")
      (value "10K")
      (footprint "easyedapro:R0603")
      (description "DNI")
      (libsource (lib "easyedapro") (part "Res"))
    )
    (comp (ref "R63")
      (value "150Ω")
      (footprint "easyedapro:R0603")
      (fields
        (field (name "Manufacturer Part") "0603WAF1500T5E")
        (field (name "Manufacturer") "UNI-ROYAL(厚声)")
      )
      (libsource (lib "easyedapro") (part "0603WAF1500T5E"))
    )
    (comp (ref "R64")
      (value "10K")
      (footprint "easyedapro:R0603")
      (description "DNI")
      (libsource (lib "easyedapro") (part "Res"))
    )
    (comp (ref "R65")
      (value "150Ω")
      (footprint "easyedapro:R0603")
      (fields
        (field (name "Manufacturer Part") "0603WAF1500T5E")
        (field (name "Manufacturer") "UNI-ROYAL(厚声)")
      )
      (libsource (lib "easyedapro") (part "0603WAF1500T5E"))
    )
    (comp (ref "R66")
      (value "10K")
      (footprint "easyedapro:R0603")
      (description "DNI")
      (libsource (lib "easyedapro") (part "Res"))
    )
    (comp (ref "R82")
      (value "4.7kΩ")
      (footprint "easyedapro:R0603")
      (fields (field (name "Manufacturer Part") "RC0603FR-074K7L") (field (name "Manufacturer") "YAGEO(国巨)"))
      (libsource (lib "easyedapro") (part "RC0603FR-074K7L"))
    )
    (comp (ref "R84")
      (value "10K")
      (footprint "easyedapro:R0603")
      (description "DNI")
      (libsource (lib "easyedapro") (part "Res"))
    )
    (comp (ref "R85")
      (value "22kΩ")
      (footprint "easyedapro:R0603")
      (fields
        (field (name "Manufacturer Part") "0603WAF2202T5E")
        (field (name "Manufacturer") "UNI-ROYAL(厚声)")
      )
      (libsource (lib "easyedapro") (part "0603WAF2202T5E"))
    )
    (comp (ref "R92")
      (value "10K")
      (footprint "easyedapro:R0603")
      (description "DNI")
      (libsource (lib "easyedapro") (part "Res"))
    )
    (comp (ref "R93")
      (value "22kΩ")
      (footprint "easyedapro:R0603")
      (fields
        (field (name "Manufacturer Part") "0603WAF2202T5E")
        (field (name "Manufacturer") "UNI-ROYAL(厚声)")
      )
      (libsource (lib "easyedapro") (part "0603WAF2202T5E"))
    )
    (comp (ref "U12")
      (value "HIR7373C")
      (footprint "easyedapro:LED-TH_BD5.0-P2.54-L-RD")
      (fields (field (name "Manufacturer") "EVERLIGHT(亿光)") (field (name "DNI") "IR LED"))
      (libsource (lib "easyedapro") (part "HIR7373C"))
    )
    (comp (ref "U13")
      (value "DY-PD333-3B-L3")
      (footprint "easyedapro:LED-TH_BD5.0-P2.54-FD")
      (fields (field (name "Manufacturer") "TONYU(东裕)") (field (name "DNI") "Detector"))
      (libsource (lib "easyedapro") (part "DY-PD333-3B-L3"))
    )
    (comp (ref "U14")
      (value "HIR7373C")
      (footprint "easyedapro:LED-TH_BD5.0-P2.54-L-RD")
      (fields (field (name "Manufacturer") "EVERLIGHT(亿光)") (field (name "DNI") "IR LED"))
      (libsource (lib "easyedapro") (part "HIR7373C"))
    )
    (comp (ref "U15")
      (value "DY-PD333-3B-L3")
      (footprint "easyedapro:LED-TH_BD5.0-P2.54-FD")
      (fields (field (name "Manufacturer") "TONYU(东裕)") (field (name "DNI") "Detector"))
      (libsource (lib "easyedapro") (part "DY-PD333-3B-L3"))
    )
    (comp (ref "U16")
      (value "HIR7373C")
      (footprint "easyedapro:LED-TH_BD5.0-P2.54-L-RD")
      (fields (field (name "Manufacturer") "EVERLIGHT(亿光)") (field (name "DNI") "IR LED"))
      (libsource (lib "easyedapro") (part "HIR7373C"))
    )
    (comp (ref "U17")
      (value "DY-PD333-3B-L3")
      (footprint "easyedapro:LED-TH_BD5.0-P2.54-FD")
      (fields (field (name "Manufacturer") "TONYU(东裕)") (field (name "DNI") "Detector"))
      (libsource (lib "easyedapro") (part "DY-PD333-3B-L3"))
    )
    (comp (ref "U18")
      (value "HIR7373C")
      (footprint "easyedapro:LED-TH_BD5.0-P2.54-L-RD")
      (fields (field (name "Manufacturer") "EVERLIGHT(亿光)") (field (name "DNI") "IR LED"))
      (libsource (lib "easyedapro") (part "HIR7373C"))
    )
    (comp (ref "U19")
      (value "DY-PD333-3B-L3")
      (footprint "easyedapro:LED-TH_BD5.0-P2.54-FD")
      (fields (field (name "Manufacturer") "TONYU(东裕)") (field (name "DNI") "Detector"))
      (libsource (lib "easyedapro") (part "DY-PD333-3B-L3"))
    )
    (comp (ref "U20")
      (value "HIR7373C")
      (footprint "easyedapro:LED-TH_BD5.0-P2.54-L-RD")
      (fields (field (name "Manufacturer") "EVERLIGHT(亿光)") (field (name "DNI") "IR LED"))
      (libsource (lib "easyedapro") (part "HIR7373C"))
    )
    (comp (ref "U21")
      (value "DY-PD333-3B-L3")
      (footprint "easyedapro:LED-TH_BD5.0-P2.54-FD")
      (fields (field (name "Manufacturer") "TONYU(东裕)") (field (name "DNI") "Detector"))
      (libsource (lib "easyedapro") (part "DY-PD333-3B-L3"))
    )
    (comp (ref "U22")
      (value "HIR7373C")
      (footprint "easyedapro:LED-TH_BD5.0-P2.54-L-RD")
      (fields (field (name "Manufacturer") "EVERLIGHT(亿光)") (field (name "DNI") "IR LED"))
      (libsource (lib "easyedapro") (part "HIR7373C"))
    )
    (comp (ref "U23")
      (value "DY-PD333-3B-L3")
      (footprint "easyedapro:LED-TH_BD5.0-P2.54-FD")
      (fields (field (name "Manufacturer") "TONYU(东裕)") (field (name "DNI") "Detector"))
      (libsource (lib "easyedapro") (part "DY-PD333-3B-L3"))
    )
    (comp (ref "U25")
      (value "ACS722LLCTR-05AB-T")
      (footprint "easyedapro:SOIC-8_L4.9-W3.9-P1.27-LS6.0-BL")
      (fields (field (name "Manufacturer") "ALLEGRO(美国埃戈罗)"))
      (libsource (lib "easyedapro") (part "ACS722LLCTR-05AB-T"))
    )
    (comp (ref "U26")
      (value "ACS722LLCTR-05AB-T")
      (footprint "easyedapro:SOIC-8_L4.9-W3.9-P1.27-LS6.0-BL")
      (fields (field (name "Manufacturer") "ALLEGRO(美国埃戈罗)"))
      (libsource (lib "easyedapro") (part "ACS722LLCTR-05AB-T"))
    )
    (comp (ref "U27")
      (value "OPA344NA/250")
      (footprint "easyedapro:SOT-23-5_L3.0-W1.7-P0.95-LS2.8-BR")
      (fields (field (name "Manufacturer") "TI(德州仪器)"))
      (libsource (lib "easyedapro") (part "OPA344NA/250"))
    )
    (comp (ref "U30")
      (value "OPA344NA/250")
      (footprint "easyedapro:SOT-23-5_L3.0-W1.7-P0.95-LS2.8-BR")
      (fields (field (name "Manufacturer") "TI(德州仪器)"))
      (libsource (lib "easyedapro") (part "OPA344NA/250"))
    )
  )
  (nets
    (net (code "1") (name "+3V3") (class "Default")
      (node (ref "C17") (pin "2") (pinfunction "2_2") (pintype "input"))
      (node (ref "C43") (pin "1") (pinfunction "1_1") (pintype "input"))
      (node (ref "C54") (pin "2") (pinfunction "2_2") (pintype "input"))
      (node (ref "C55") (pin "2") (pinfunction "2_2") (pintype "input"))
      (node (ref "C56") (pin "2") (pinfunction "2_2") (pintype "input"))
      (node (ref "C57") (pin "2") (pinfunction "2_2") (pintype "input"))
      (node (ref "C58") (pin "2") (pinfunction "2_2") (pintype "input"))
      (node (ref "H1") (pin "1") (pinfunction "1_1") (pintype "input"))
      (node (ref "L4") (pin "1") (pinfunction "1_1") (pintype "unspecified"))
      (node (ref "L5") (pin "2") (pinfunction "2_2") (pintype "unspecified"))
      (node (ref "P1") (pin "3") (pinfunction "3_3") (pintype "input"))
      (node (ref "P2") (pin "3") (pinfunction "3_3") (pintype "input"))
      (node (ref "R52") (pin "2") (pinfunction "2_2") (pintype "input"))
      (node (ref "R53") (pin "2") (pinfunction "2_2") (pintype "input"))
      (node (ref "R54") (pin "2") (pinfunction "2_2") (pintype "input"))
      (node (ref "U1") (pin "1") (pinfunction "VBAT_1") (pintype "unspecified"))
      (node (ref "U1") (pin "19") (pinfunction "VDD_19") (pintype "unspecified"))
      (node (ref "U1") (pin "32") (pinfunction "VDD_32") (pintype "unspecified"))
      (node (ref "U1") (pin "48") (pinfunction "VDD_48") (pintype "unspecified"))
      (node (ref "U1") (pin "64") (pinfunction "VDD_64") (pintype "unspecified"))
      (node (ref "U10") (pin "19") (pinfunction "STBY_19") (pintype "unspecified"))
      (node (ref "U6") (pin "4") (pinfunction "VOUT_4") (pintype "unspecified"))
    )
    (net (code "2") (name "+5V") (class "Default")
      (node (ref "C15") (pin "2") (pinfunction "2_2") (pintype "input"))
      (node (ref "C52") (pin "2") (pinfunction "2_2") (pintype "input"))
      (node (ref "C53") (pin "2") (pinfunction "2_2") (pintype "input"))
      (node (ref "C81") (pin "1") (pinfunction "1_1") (pintype "input"))
      (node (ref "C83") (pin "1") (pinfunction "1_1") (pintype "input"))
      (node (ref "L6") (pin "1") (pinfunction "1_1") (pintype "unspecified"))
      (node (ref "L7") (pin "1") (pinfunction "1_1") (pintype "unspecified"))
      (node (ref "R82") (pin "2") (pinfunction "2_2") (pintype "input"))
      (node (ref "R9") (pin "2") (pinfunction "2_2") (pintype "input"))
      (node (ref "U25") (pin "8") (pinfunction "VCC_8") (pintype "input"))
      (node (ref "U26") (pin "8") (pinfunction "VCC_8") (pintype "input"))
      (node (ref "U27") (pin "5") (pinfunction "V+_5") (pintype "unspecified"))
      (node (ref "U30") (pin "5") (pinfunction "V+_5") (pintype "unspecified"))
      (node (ref "U4") (pin "1") (pinfunction "S_1") (pintype "unspecified"))
      (node (ref "U4") (pin "2") (pinfunction "S_2") (pintype "unspecified"))
      (node (ref "U4") (pin "3") (pinfunction "S_3") (pintype "unspecified"))
      (node (ref "U6") (pin "1") (pinfunction "EN_1") (pintype "unspecified"))
      (node (ref "U6") (pin "6") (pinfunction "VIN_6") (pintype "unspecified"))
    )
    (net (code "3") (name "+5V_MOT") (class "Default")
      (node (ref "C46") (pin "1") (pinfunction "1_1") (pintype "input"))
      (node (ref "C65") (pin "2") (pinfunction "2_2") (pintype "input"))
      (node (ref "L6") (pin "2") (pinfunction "2_2") (pintype "unspecified"))
      (node (ref "L7") (pin "2") (pinfunction "2_2") (pintype "unspecified"))
      (node (ref "U10") (pin "13") (pinfunction "VM2_13") (pintype "unspecified"))
      (node (ref "U10") (pin "14") (pinfunction "VM3_14") (pintype "unspecified"))
      (node (ref "U10") (pin "24") (pinfunction "VM1_24") (pintype "unspecified"))
    )
    (net (code "4") (name "5V_UP") (class "Default")
      (node (ref "C48") (pin "2") (pinfunction "2_2") (pintype "input"))
      (node (ref "C49") (pin "2") (pinfunction "2_2") (pintype "input"))
      (node (ref "C7") (pin "2") (pinfunction "2_2") (pintype "input"))
      (node (ref "C8") (pin "2") (pinfunction "2_2") (pintype "input"))
      (node (ref "D1") (pin "2") (pinfunction "2_2") (pintype "input"))
      (node (ref "F1") (pin "2") (pinfunction "2_2") (pintype "unspecified"))
      (node (ref "L2") (pin "1") (pinfunction "1_1") (pintype "unspecified"))
      (node (ref "L3") (pin "1") (pinfunction "1_1") (pintype "unspecified"))
      (node (ref "U3") (pin "7") (pinfunction "OUT_7") (pintype "unspecified"))
    )
    (net (code "5") (name "AGND") (class "Default")
      (node (ref "C46") (pin "2") (pinfunction "2_2") (pintype "input"))
      (node (ref "C65") (pin "1") (pinfunction "1_1") (pintype "input"))
      (node (ref "L8") (pin "2") (pinfunction "2_2") (pintype "unspecified"))
      (node (ref "L9") (pin "2") (pinfunction "2_2") (pintype "unspecified"))
      (node (ref "U10") (pin "10") (pinfunction "PGND2_10") (pintype "unspecified"))
      (node (ref "U10") (pin "3") (pinfunction "PGND1_3") (pintype "unspecified"))
      (node (ref "U10") (pin "4") (pinfunction "PGND1_4") (pintype "unspecified"))
      (node (ref "U10") (pin "9") (pinfunction "PGND2_9") (pintype "unspecified"))
    )
    (net (code "6") (name "BOOT_O") (class "Default")
      (node (ref "R55") (pin "1") (pinfunction "1_1") (pintype "input"))
      (node (ref "U1") (pin "60") (pinfunction "BOOT0_60") (pintype "unspecified"))
    )
    (net (code "7") (name "BTN_02") (class "Default")
      (node (ref "C67") (pin "2") (pinfunction "2_2") (pintype "input"))
      (node (ref "R53") (pin "1") (pinfunction "1_1") (pintype "input"))
      (node (ref "R77") (pin "1") (pinfunction "1_1") (pintype "input"))
      (node (ref "U1") (pin "27") (pinfunction "PB1_27") (pintype "unspecified"))
    )
    (net (code "8") (name "BTN_03") (class "Default")
      (node (ref "C68") (pin "2") (pinfunction "2_2") (pintype "input"))
      (node (ref "R54") (pin "1") (pinfunction "1_1") (pintype "input"))
      (node (ref "R78") (pin "1") (pinfunction "1_1") (pintype "input"))
      (node (ref "U1") (pin "28") (pinfunction "PB2_28") (pintype "unspecified"))
    )
    (net (code "9") (name "CRS_O1") (class "Default")
      (node (ref "C76") (pin "2") (pinfunction "2_2") (pintype "input"))
      (node (ref "R85") (pin "2") (pinfunction "2_2") (pintype "input"))
      (node (ref "U1") (pin "24") (pinfunction "PC4_24") (pintype "unspecified"))
      (node (ref "U27") (pin "1") (pinfunction "OUT_1") (pintype "output"))
    )
    (net (code "10") (name "CRS_O2") (class "Default")
      (node (ref "C82") (pin "2") (pinfunction "2_2") (pintype "input"))
      (node (ref "R93") (pin "2") (pinfunction "2_2") (pintype "input"))
      (node (ref "U1") (pin "25") (pinfunction "PC5_25") (pintype "unspecified"))
      (node (ref "U30") (pin "1") (pinfunction "OUT_1") (pintype "output"))
    )
    (net (code "11") (name "CRS_VIOUT1") (class "Default")
      (node (ref "R84") (pin "2") (pinfunction "2_2") (pintype "input"))
      (node (ref "U25") (pin "7") (pinfunction "VIOUT_7") (pintype "input"))
    )
    (net (code "12") (name "CRS_VIOUT2") (class "Default")
      (node (ref "R92") (pin "2") (pinfunction "2_2") (pintype "input"))
      (node (ref "U26") (pin "7") (pinfunction "VIOUT_7") (pintype "input"))
    )
    (net (code "13") (name "ENC_OUT_A1") (class "Default")
      (node (ref "P1") (pin "4") (pinfunction "4_4") (pintype "input"))
      (node (ref "U1") (pin "22") (pinfunction "PA6_22") (pintype "unspecified"))
    )
    (net (code "14") (name "ENC_OUT_A2") (class "Default")
      (node (ref "P2") (pin "4") (pinfunction "4_4") (pintype "input"))
      (node (ref "U1") (pin "41") (pinfunction "PA8_41") (pintype "unspecified"))
    )
    (net (code "15") (name "ENC_OUT_B1") (class "Default")
      (node (ref "P1") (pin "5") (pinfunction "5_5") (pintype "input"))
      (node (ref "U1") (pin "23") (pinfunction "PA7_23") (pintype "unspecified"))
    )
    (net (code "16") (name "ENC_OUT_B2") (class "Default")
      (node (ref "P2") (pin "5") (pinfunction "5_5") (pintype "input"))
      (node (ref "U1") (pin "42") (pinfunction "PA9_42") (pintype "unspecified"))
    )
    (net (code "17") (name "GND") (class "Default")
      (node (ref "C10") (pin "1") (pinfunction "1_1") (pintype "input"))
      (node (ref "C11") (pin "1") (pinfunction "1_1") (pintype "input"))
      (node (ref "C15") (pin "1") (pinfunction "1_1") (pintype "input"))
      (node (ref "C17") (pin "1") (pinfunction "1_1") (pintype "input"))
      (node (ref "C43") (pin "2") (pinfunction "2_2") (pintype "input"))
      (node (ref "C48") (pin "1") (pinfunction "1_1") (pintype "input"))
      (node (ref "C49") (pin "1") (pinfunction "1_1") (pintype "input"))
      (node (ref "C50") (pin "1") (pinfunction "1_1") (pintype "input"))
      (node (ref "C51") (pin "1") (pinfunction "1_1") (pintype "input"))
      (node (ref "C52") (pin "1") (pinfunction "1_1") (pintype "input"))
      (node (ref "C53") (pin "1") (pinfunction "1_1") (pintype "input"))
      (node (ref "C54") (pin "1") (pinfunction "1_1") (pintype "input"))
      (node (ref "C55") (pin "1") (pinfunction "1_1") (pintype "input"))
      (node (ref "C56") (pin "1") (pinfunction "1_1") (pintype "input"))
      (node (ref "C57") (pin "1") (pinfunction "1_1") (pintype "input"))
      (node (ref "C58") (pin "1") (pinfunction "1_1") (pintype "input"))
      (node (ref "C66") (pin "1") (pinfunction "1_1") (pintype "input"))
      (node (ref "C67") (pin "1") (pinfunction "1_1") (pintype "input"))
      (node (ref "C68") (pin "1") (pinfunction "1_1") (pintype "input"))
      (node (ref "C7") (pin "1") (pinfunction "1_1") (pintype "input"))
      (node (ref "C74") (pin "1") (pinfunction "1_1") (pintype "input"))
      (node (ref "C79") (pin "1") (pinfunction "1_1") (pintype "input"))
      (node (ref "C8") (pin "1") (pinfunction "1_1") (pintype "input"))
      (node (ref "C80") (pin "1") (pinfunction "1_1") (pintype "input"))
      (node (ref "C81") (pin "2") (pinfunction "2_2") (pintype "input"))
      (node (ref "C83") (pin "2") (pinfunction "2_2") (pintype "input"))
      (node (ref "C84") (pin "1") (pinfunction "1_1") (pintype "input"))
      (node (ref "C9") (pin "1") (pinfunction "1_1") (pintype "input"))
      (node (ref "D1") (pin "1") (pinfunction "1_1") (pintype "input"))
      (node (ref "D2") (pin "2") (pinfunction "A_2") (pintype "unspecified"))
      (node (ref "L8") (pin "1") (pinfunction "1_1") (pintype "unspecified"))
      (node (ref "L9") (pin "1") (pinfunction "1_1") (pintype "unspecified"))
      (node (ref "LED6") (pin "2") (pinfunction "K_2") (pintype "unspecified"))
      (node (ref "LED7") (pin "2") (pinfunction "K_2") (pintype "unspecified"))
      (node (ref "LED8") (pin "2") (pinfunction "K_2") (pintype "unspecified"))
      (node (ref "LED9") (pin "2") (pinfunction "K_2") (pintype "unspecified"))
      (node (ref "P1") (pin "6") (pinfunction "6_6") (pintype "input"))
      (node (ref "P2") (pin "6") (pinfunction "6_6") (pintype "input"))
      (node (ref "P3") (pin "6") (pinfunction "6_6") (pintype "input"))
      (node (ref "R55") (pin "2") (pinfunction "2_2") (pintype "input"))
      (node (ref "R68") (pin "1") (pinfunction "1_1") (pintype "input"))
      (node (ref "R71") (pin "1") (pinfunction "1_1") (pintype "input"))
      (node (ref "R74") (pin "1") (pinfunction "1_1") (pintype "input"))
      (node (ref "R75") (pin "1") (pinfunction "1_1") (pintype "input"))
      (node (ref "SW2") (pin "2") (pinfunction "2_2") (pintype "input"))
      (node (ref "SW3") (pin "2") (pinfunction "2_2") (pintype "input"))
      (node (ref "SW4") (pin "2") (pinfunction "2_2") (pintype "input"))
      (node (ref "U1") (pin "12") (pinfunction "VSSA/VREF-_12") (pintype "unspecified"))
      (node (ref "U1") (pin "18") (pinfunction "VSS_18") (pintype "unspecified"))
      (node (ref "U1") (pin "30") (pinfunction "VCAP_1_30") (pintype "unspecified"))
      (node (ref "U1") (pin "31") (pinfunction "VSS_31") (pintype "unspecified"))
      (node (ref "U1") (pin "47") (pinfunction "VSS_47") (pintype "unspecified"))
      (node (ref "U1") (pin "63") (pinfunction "VSS_63") (pintype "unspecified"))
      (node (ref "U10") (pin "18") (pinfunction "GND_18") (pintype "unspecified"))
      (node (ref "U12") (pin "1") (pinfunction "1_1") (pintype "unspecified"))
      (node (ref "U13") (pin "1") (pinfunction "1_1") (pintype "input"))
      (node (ref "U14") (pin "1") (pinfunction "1_1") (pintype "unspecified"))
      (node (ref "U15") (pin "1") (pinfunction "1_1") (pintype "input"))
      (node (ref "U16") (pin "1") (pinfunction "1_1") (pintype "unspecified"))
      (node (ref "U17") (pin "1") (pinfunction "1_1") (pintype "input"))
      (node (ref "U18") (pin "1") (pinfunction "1_1") (pintype "unspecified"))
      (node (ref "U19") (pin "1") (pinfunction "1_1") (pintype "input"))
      (node (ref "U20") (pin "1") (pinfunction "1_1") (pintype "unspecified"))
      (node (ref "U21") (pin "1") (pinfunction "1_1") (pintype "input"))
      (node (ref "U22") (pin "1") (pinfunction "1_1") (pintype "unspecified"))
      (node (ref "U23") (pin "1") (pinfunction "1_1") (pintype "input"))
      (node (ref "U24") (pin "2") (pinfunction "2_2") (pintype "unspecified"))
      (node (ref "U25") (pin "5") (pinfunction "GND_5") (pintype "input"))
      (node (ref "U26") (pin "5") (pinfunction "GND_5") (pintype "input"))
      (node (ref "U27") (pin "2") (pinfunction "V-_2") (pintype "unspecified"))
      (node (ref "U27") (pin "3") (pinfunction "IN+_3") (pintype "unspecified"))
      (node (ref "U3") (pin "8") (pinfunction "PGND_8") (pintype "unspecified"))
      (node (ref "U3") (pin "9") (pinfunction "AGND_9") (pintype "unspecified"))
      (node (ref "U30") (pin "2") (pinfunction "V-_2") (pintype "unspecified"))
      (node (ref "U30") (pin "3") (pinfunction "IN+_3") (pintype "unspecified"))
      (node (ref "U31") (pin "2") (pinfunction "S_2") (pintype "unspecified"))
      (node (ref "U6") (pin "2") (pinfunction "GND_2") (pintype "unspecified"))
      (node (ref "U6") (pin "7") (pinfunction "EXP_7") (pintype "unspecified"))
      (node (ref "USB1") (pin "1") (pinfunction "GND_1") (pintype "unspecified"))
      (node (ref "USB1") (pin "12") (pinfunction "GND_12") (pintype "unspecified"))
      (node (ref "USB1") (pin "13") (pinfunction "SHELL_13") (pintype "unspecified"))
      (node (ref "USB1") (pin "14") (pinfunction "SHELL_14") (pintype "unspecified"))
    )
    (net (code "18") (name "IR_S_IN1") (class "Default")
      (node (ref "R49") (pin "1") (pinfunction "1_1") (pintype "input"))
      (node (ref "R50") (pin "1") (pinfunction "1_1") (pintype "input"))
      (node (ref "U1") (pin "59") (pinfunction "PB7_59") (pintype "unspecified"))
    )
    (net (code "19") (name "IR_S_IN2") (class "Default")
      (node (ref "R57") (pin "1") (pinfunction "1_1") (pintype "input"))
      (node (ref "R58") (pin "1") (pinfunction "1_1") (pintype "input"))
      (node (ref "U1") (pin "2") (pinfunction "PC13_2") (pintype "unspecified"))
    )
    (net (code "20") (name "IR_S_IN3") (class "Default")
      (node (ref "R59") (pin "1") (pinfunction "1_1") (pintype "input"))
      (node (ref "R60") (pin "1") (pinfunction "1_1") (pintype "input"))
      (node (ref "U1") (pin "51") (pinfunction "PC10_51") (pintype "unspecified"))
    )
    (net (code "21") (name "IR_S_IN4") (class "Default")
      (node (ref "R61") (pin "1") (pinfunction "1_1") (pintype "input"))
      (node (ref "R62") (pin "1") (pinfunction "1_1") (pintype "input"))
      (node (ref "U1") (pin "52") (pinfunction "PC11_52") (pintype "unspecified"))
    )
    (net (code "22") (name "IR_S_IN5") (class "Default")
      (node (ref "R63") (pin "1") (pinfunction "1_1") (pintype "input"))
      (node (ref "R64") (pin "1") (pinfunction "1_1") (pintype "input"))
      (node (ref "U1") (pin "10") (pinfunction "PC2_10") (pintype "unspecified"))
    )
    (net (code "23") (name "IR_S_IN6") (class "Default")
      (node (ref "R65") (pin "1") (pinfunction "1_1") (pintype "input"))
      (node (ref "R66") (pin "1") (pinfunction "1_1") (pintype "input"))
      (node (ref "U1") (pin "11") (pinfunction "PC3_11") (pintype "unspecified"))
    )
    (net (code "24") (name "IR_S_OUT1") (class "Default")
      (node (ref "R50") (pin "2") (pinfunction "2_2") (pintype "input"))
      (node (ref "U1") (pin "14") (pinfunction "PA0_14") (pintype "unspecified"))
      (node (ref "U13") (pin "2") (pinfunction "2_2") (pintype "input"))
    )
    (net (code "25") (name "IR_S_OUT2") (class "Default")
      (node (ref "R58") (pin "2") (pinfunction "2_2") (pintype "input"))
      (node (ref "U1") (pin "15") (pinfunction "PA1_15") (pintype "unspecified"))
      (node (ref "U15") (pin "2") (pinfunction "2_2") (pintype "input"))
    )
    (net (code "26") (name "IR_S_OUT3") (class "Default")
      (node (ref "R60") (pin "2") (pinfunction "2_2") (pintype "input"))
      (node (ref "U1") (pin "20") (pinfunction "PA4_20") (pintype "unspecified"))
      (node (ref "U17") (pin "2") (pinfunction "2_2") (pintype "input"))
    )
    (net (code "27") (name "IR_S_OUT4") (class "Default")
      (node (ref "R62") (pin "2") (pinfunction "2_2") (pintype "input"))
      (node (ref "U1") (pin "26") (pinfunction "PB0_26") (pintype "unspecified"))
      (node (ref "U19") (pin "2") (pinfunction "2_2") (pintype "input"))
    )
    (net (code "28") (name "IR_S_OUT5") (class "Default")
      (node (ref "R64") (pin "2") (pinfunction "2_2") (pintype "input"))
      (node (ref "U1") (pin "9") (pinfunction "PC1_9") (pintype "unspecified"))
      (node (ref "U21") (pin "2") (pinfunction "2_2") (pintype "input"))
    )
    (net (code "29") (name "IR_S_OUT6") (class "Default")
      (node (ref "R66") (pin "2") (pinfunction "2_2") (pintype "input"))
      (node (ref "U1") (pin "8") (pinfunction "PC0_8") (pintype "unspecified"))
      (node (ref "U23") (pin "2") (pinfunction "2_2") (pintype "input"))
    )
    (net (code "30") (name "LED1") (class "Default")
      (node (ref "R72") (pin "1") (pinfunction "1_1") (pintype "input"))
      (node (ref "U3") (pin "2") (pinfunction "LED1_2") (pintype "unspecified"))
    )
    (net (code "31") (name "LED2") (class "Default")
      (node (ref "R73") (pin "1") (pinfunction "1_1") (pintype "input"))
      (node (ref "U3") (pin "3") (pinfunction "LED2_3") (pintype "unspecified"))
    )
    (net (code "32") (name "LED3") (class "Default")
      (node (ref "LED10") (pin "2") (pinfunction "K_2") (pintype "unspecified"))
      (node (ref "LED11") (pin "1") (pinfunction "A_1") (pintype "unspecified"))
      (node (ref "LED12") (pin "2") (pinfunction "K_2") (pintype "unspecified"))
      (node (ref "LED13") (pin "1") (pinfunction "A_1") (pintype "unspecified"))
      (node (ref "U3") (pin "4") (pinfunction "LED3_4") (pintype "unspecified"))
    )
    (net (code "33") (name "LIPO+") (class "Default")
      (node (ref "C50") (pin "2") (pinfunction "2_2") (pintype "input"))
      (node (ref "C51") (pin "2") (pinfunction "2_2") (pintype "input"))
      (node (ref "F2") (pin "1") (pinfunction "1_1") (pintype "unspecified"))
      (node (ref "L1") (pin "1") (pinfunction "1_1") (pintype "input"))
      (node (ref "U3") (pin "6") (pinfunction "BAT_6") (pintype "unspecified"))
    )
    (net (code "34") (name "M_AIN1") (class "Default")
      (node (ref "U1") (pin "43") (pinfunction "PA10_43") (pintype "unspecified"))
      (node (ref "U10") (pin "21") (pinfunction "AIN1_21") (pintype "unspecified"))
    )
    (net (code "35") (name "M_AIN2") (class "Default")
      (node (ref "U1") (pin "40") (pinfunction "PC9_40") (pintype "unspecified"))
      (node (ref "U10") (pin "22") (pinfunction "AIN2_22") (pintype "unspecified"))
    )
    (net (code "36") (name "M_AO1") (class "Default")
      (node (ref "R88") (pin "1") (pinfunction "1_1") (pintype "input"))
      (node (ref "R90") (pin "1") (pinfunction "1_1") (pintype "input"))
      (node (ref "U10") (pin "1") (pinfunction "AO1_1") (pintype "unspecified"))
      (node (ref "U10") (pin "2") (pinfunction "AO1_2") (pintype "unspecified"))
    )
    (net (code "37") (name "M_AO2") (class "Default")
      (node (ref "P1") (pin "2") (pinfunction "2_2") (pintype "input"))
      (node (ref "U10") (pin "5") (pinfunction "AO2_5") (pintype "unspecified"))
      (node (ref "U10") (pin "6") (pinfunction "AO2_6") (pintype "unspecified"))
    )
    (net (code "38") (name "M_BIN1") (class "Default")
      (node (ref "U1") (pin "57") (pinfunction "PB5_57") (pintype "unspecified"))
      (node (ref "U10") (pin "17") (pinfunction "BIN1_17") (pintype "unspecified"))
    )
    (net (code "39") (name "M_BIN2") (class "Default")
      (node (ref "U1") (pin "39") (pinfunction "PC8_39") (pintype "unspecified"))
      (node (ref "U10") (pin "16") (pinfunction "BIN2_16") (pintype "unspecified"))
    )
    (net (code "40") (name "M_BO1") (class "Default")
      (node (ref "R89") (pin "1") (pinfunction "1_1") (pintype "input"))
      (node (ref "R91") (pin "1") (pinfunction "1_1") (pintype "input"))
      (node (ref "U10") (pin "11") (pinfunction "BO1_11") (pintype "unspecified"))
      (node (ref "U10") (pin "12") (pinfunction "BO1_12") (pintype "unspecified"))
    )
    (net (code "41") (name "M_BO2") (class "Default")
      (node (ref "P2") (pin "2") (pinfunction "2_2") (pintype "input"))
      (node (ref "U10") (pin "7") (pinfunction "BO2_7") (pintype "unspecified"))
      (node (ref "U10") (pin "8") (pinfunction "BO2_8") (pintype "unspecified"))
    )
    (net (code "42") (name "M_CURR1_IN") (class "Default")
      (node (ref "R88") (pin "2") (pinfunction "2_2") (pintype "input"))
      (node (ref "U25") (pin "1") (pinfunction "IP+_1") (pintype "input"))
      (node (ref "U25") (pin "2") (pinfunction "IP+_2") (pintype "input"))
    )
    (net (code "43") (name "M_CURR1_OUT") (class "Default")
      (node (ref "U25") (pin "3") (pinfunction "IP–_3") (pintype "input"))
      (node (ref "U25") (pin "4") (pinfunction "IP–_4") (pintype "input"))
      (node (ref "U29") (pin "1") (pinfunction "1_1") (pintype "unspecified"))
    )
    (net (code "44") (name "M_CURR2_IN") (class "Default")
      (node (ref "R89") (pin "2") (pinfunction "2_2") (pintype "input"))
      (node (ref "U26") (pin "1") (pinfunction "IP+_1") (pintype "input"))
      (node (ref "U26") (pin "2") (pinfunction "IP+_2") (pintype "input"))
    )
    (net (code "45") (name "M_CURR2_OUT") (class "Default")
      (node (ref "U26") (pin "3") (pinfunction "IP–_3") (pintype "input"))
      (node (ref "U26") (pin "4") (pinfunction "IP–_4") (pintype "input"))
      (node (ref "U29") (pin "2") (pinfunction "2_2") (pintype "unspecified"))
    )
    (net (code "46") (name "M_PWMA") (class "Default")
      (node (ref "U1") (pin "61") (pinfunction "PB8_61") (pintype "unspecified"))
      (node (ref "U10") (pin "23") (pinfunction "PWMA_23") (pintype "unspecified"))
    )
    (net (code "47") (name "M_PWMB") (class "Default")
      (node (ref "U1") (pin "62") (pinfunction "PB9_62") (pintype "unspecified"))
      (node (ref "U10") (pin "15") (pinfunction "PWMB_15") (pintype "unspecified"))
    )
    (net (code "48") (name "Net-(D2-K)") (class "Default")
      (node (ref "C10") (pin "2") (pinfunction "2_2") (pintype "input"))
      (node (ref "C11") (pin "2") (pinfunction "2_2") (pintype "input"))
      (node (ref "C9") (pin "2") (pinfunction "2_2") (pintype "input"))
      (node (ref "D2") (pin "1") (pinfunction "K_1") (pintype "unspecified"))
      (node (ref "L2") (pin "2") (pinfunction "2_2") (pintype "unspecified"))
      (node (ref "L3") (pin "2") (pinfunction "2_2") (pintype "unspecified"))
      (node (ref "R51") (pin "2") (pinfunction "2_2") (pintype "input"))
      (node (ref "R69") (pin "2") (pinfunction "2_2") (pintype "input"))
      (node (ref "U4") (pin "5") (pinfunction "D_5") (pintype "unspecified"))
      (node (ref "U4") (pin "6") (pinfunction "D_6") (pintype "unspecified"))
      (node (ref "U4") (pin "7") (pinfunction "D_7") (pintype "unspecified"))
      (node (ref "U4") (pin "8") (pinfunction "D_8") (pintype "unspecified"))
      (node (ref "U4") (pin "9") (pinfunction "D_9") (pintype "unspecified"))
    )
    (net (code "49") (name "Net-(F1-Pad1)") (class "Default")
      (node (ref "F1") (pin "1") (pinfunction "1_1") (pintype "unspecified"))
      (node (ref "USB1") (pin "11") (pinfunction "VBUS_11") (pintype "unspecified"))
      (node (ref "USB1") (pin "2") (pinfunction "VBUS_2") (pintype "unspecified"))
    )
    (net (code "50") (name "Net-(F2-Pad2)") (class "Default")
      (node (ref "F2") (pin "2") (pinfunction "2_2") (pintype "unspecified"))
      (node (ref "U24") (pin "1") (pinfunction "1_1") (pintype "unspecified"))
    )
    (net (code "51") (name "Net-(LED6-A)") (class "Default")
      (node (ref "LED6") (pin "1") (pinfunction "A_1") (pintype "unspecified"))
      (node (ref "R9") (pin "1") (pinfunction "1_1") (pintype "input"))
    )
    (net (code "52") (name "Net-(LED7-A)") (class "Default")
      (node (ref "LED7") (pin "1") (pinfunction "A_1") (pintype "unspecified"))
      (node (ref "R46") (pin "1") (pinfunction "1_1") (pintype "input"))
    )
    (net (code "53") (name "Net-(LED8-A)") (class "Default")
      (node (ref "LED8") (pin "1") (pinfunction "A_1") (pintype "unspecified"))
      (node (ref "R47") (pin "1") (pinfunction "1_1") (pintype "input"))
    )
    (net (code "54") (name "Net-(LED9-A)") (class "Default")
      (node (ref "LED9") (pin "1") (pinfunction "A_1") (pintype "unspecified"))
      (node (ref "R48") (pin "1") (pinfunction "1_1") (pintype "input"))
    )
    (net (code "55") (name "Net-(LED10-A)") (class "Default")
      (node (ref "LED10") (pin "1") (pinfunction "A_1") (pintype "unspecified"))
      (node (ref "LED13") (pin "2") (pinfunction "K_2") (pintype "unspecified"))
      (node (ref "R73") (pin "2") (pinfunction "2_2") (pintype "input"))
    )
    (net (code "56") (name "Net-(LED11-K)") (class "Default")
      (node (ref "LED11") (pin "2") (pinfunction "K_2") (pintype "unspecified"))
      (node (ref "LED12") (pin "1") (pinfunction "A_1") (pintype "unspecified"))
      (node (ref "R72") (pin "2") (pinfunction "2_2") (pintype "input"))
    )
    (net (code "57") (name "Net-(P1-Pad1)") (class "Default")
      (node (ref "P1") (pin "1") (pinfunction "1_1") (pintype "input"))
      (node (ref "R90") (pin "2") (pinfunction "2_2") (pintype "input"))
    )
    (net (code "58") (name "Net-(P2-Pad1)") (class "Default")
      (node (ref "P2") (pin "1") (pinfunction "1_1") (pintype "input"))
      (node (ref "R91") (pin "2") (pinfunction "2_2") (pintype "input"))
    )
    (net (code "59") (name "Net-(R49-Pad2)") (class "Default")
      (node (ref "R49") (pin "2") (pinfunction "2_2") (pintype "input"))
      (node (ref "U12") (pin "2") (pinfunction "2_2") (pintype "unspecified"))
    )
    (net (code "60") (name "Net-(R51-Pad1)") (class "Default")
      (node (ref "R51") (pin "1") (pinfunction "1_1") (pintype "input"))
      (node (ref "SW1") (pin "1") (pinfunction "1_1") (pintype "input"))
    )
    (net (code "61") (name "Net-(R57-Pad2)") (class "Default")
      (node (ref "R57") (pin "2") (pinfunction "2_2") (pintype "input"))
      (node (ref "U14") (pin "2") (pinfunction "2_2") (pintype "unspecified"))
    )
    (net (code "62") (name "Net-(R59-Pad2)") (class "Default")
      (node (ref "R59") (pin "2") (pinfunction "2_2") (pintype "input"))
      (node (ref "U16") (pin "2") (pinfunction "2_2") (pintype "unspecified"))
    )
    (net (code "63") (name "Net-(R61-Pad2)") (class "Default")
      (node (ref "R61") (pin "2") (pinfunction "2_2") (pintype "input"))
      (node (ref "U18") (pin "2") (pinfunction "2_2") (pintype "unspecified"))
    )
    (net (code "64") (name "Net-(R63-Pad2)") (class "Default")
      (node (ref "R63") (pin "2") (pinfunction "2_2") (pintype "input"))
      (node (ref "U20") (pin "2") (pinfunction "2_2") (pintype "unspecified"))
    )
    (net (code "65") (name "Net-(R65-Pad2)") (class "Default")
      (node (ref "R65") (pin "2") (pinfunction "2_2") (pintype "input"))
      (node (ref "U22") (pin "2") (pinfunction "2_2") (pintype "unspecified"))
    )
    (net (code "66") (name "Net-(R70-Pad1)") (class "Default")
      (node (ref "R70") (pin "1") (pinfunction "1_1") (pintype "input"))
      (node (ref "SW1") (pin "2") (pinfunction "2_2") (pintype "input"))
    )
    (net (code "67") (name "Net-(R76-Pad2)") (class "Default")
      (node (ref "R76") (pin "2") (pinfunction "2_2") (pintype "input"))
      (node (ref "SW4") (pin "3") (pinfunction "3_3") (pintype "input"))
    )
    (net (code "68") (name "Net-(R77-Pad2)") (class "Default")
      (node (ref "R77") (pin "2") (pinfunction "2_2") (pintype "input"))
      (node (ref "SW2") (pin "3") (pinfunction "3_3") (pintype "input"))
    )
    (net (code "69") (name "Net-(R78-Pad2)") (class "Default")
      (node (ref "R78") (pin "2") (pinfunction "2_2") (pintype "input"))
      (node (ref "SW3") (pin "3") (pinfunction "3_3") (pintype "input"))
    )
    (net (code "70") (name "Net-(U1-VDDA{slash}VREF+)") (class "Default")
      (node (ref "L4") (pin "2") (pinfunction "2_2") (pintype "unspecified"))
      (node (ref "U1") (pin "13") (pinfunction "VDDA/VREF+_13") (pintype "unspecified"))
    )
    (net (code "71") (name "Net-(U3-ISET)") (class "Default")
      (node (ref "R71") (pin "2") (pinfunction "2_2") (pintype "input"))
      (node (ref "U3") (pin "5") (pinfunction "ISET_5") (pintype "unspecified"))
    )
    (net (code "72") (name "Net-(U3-SW)") (class "Default")
      (node (ref "L1") (pin "2") (pinfunction "2_2") (pintype "input"))
      (node (ref "U3") (pin "1") (pinfunction "SW_1") (pintype "unspecified"))
    )
    (net (code "73") (name "Net-(U10-VCC)") (class "Default")
      (node (ref "C84") (pin "2") (pinfunction "2_2") (pintype "input"))
      (node (ref "L5") (pin "1") (pinfunction "1_1") (pintype "unspecified"))
      (node (ref "U10") (pin "20") (pinfunction "VCC_20") (pintype "unspecified"))
    )
    (net (code "74") (name "Net-(U25-BW_SEL)") (class "Default")
      (node (ref "R82") (pin "1") (pinfunction "1_1") (pintype "input"))
      (node (ref "U25") (pin "6") (pinfunction "BW_SEL_6") (pintype "input"))
      (node (ref "U26") (pin "6") (pinfunction "BW_SEL_6") (pintype "input"))
    )
    (net (code "75") (name "Net-(U27-IN-)") (class "Default")
      (node (ref "C76") (pin "1") (pinfunction "1_1") (pintype "input"))
      (node (ref "R84") (pin "1") (pinfunction "1_1") (pintype "input"))
      (node (ref "R85") (pin "1") (pinfunction "1_1") (pintype "input"))
      (node (ref "U27") (pin "4") (pinfunction "IN-_4") (pintype "unspecified"))
    )
    (net (code "76") (name "Net-(U30-IN-)") (class "Default")
      (node (ref "C82") (pin "1") (pinfunction "1_1") (pintype "input"))
      (node (ref "R92") (pin "1") (pinfunction "1_1") (pintype "input"))
      (node (ref "R93") (pin "1") (pinfunction "1_1") (pintype "input"))
      (node (ref "U30") (pin "4") (pinfunction "IN-_4") (pintype "unspecified"))
    )
    (net (code "77") (name "Net-(U31-D)") (class "Default")
      (node (ref "R69") (pin "1") (pinfunction "1_1") (pintype "input"))
      (node (ref "U31") (pin "3") (pinfunction "D_3") (pintype "unspecified"))
      (node (ref "U4") (pin "4") (pinfunction "G_4") (pintype "unspecified"))
    )
    (net (code "78") (name "Net-(U31-G)") (class "Default")
      (node (ref "C74") (pin "2") (pinfunction "2_2") (pintype "input"))
      (node (ref "R68") (pin "2") (pinfunction "2_2") (pintype "input"))
      (node (ref "R70") (pin "2") (pinfunction "2_2") (pintype "input"))
      (node (ref "U31") (pin "1") (pinfunction "G_1") (pintype "unspecified"))
    )
    (net (code "79") (name "Net-(USB1-CC1)") (class "Default")
      (node (ref "R75") (pin "2") (pinfunction "2_2") (pintype "input"))
      (node (ref "USB1") (pin "4") (pinfunction "CC1_4") (pintype "unspecified"))
    )
    (net (code "80") (name "Net-(USB1-CC2)") (class "Default")
      (node (ref "R74") (pin "2") (pinfunction "2_2") (pintype "input"))
      (node (ref "USB1") (pin "10") (pinfunction "CC2_10") (pintype "unspecified"))
    )
    (net (code "81") (name "OSC_8M_O1") (class "Default")
      (node (ref "C80") (pin "2") (pinfunction "2_2") (pintype "input"))
      (node (ref "U1") (pin "5") (pinfunction "PH0-OSC_IN_5") (pintype "unspecified"))
      (node (ref "X3") (pin "1") (pinfunction "OSC1_1") (pintype "input"))
    )
    (net (code "82") (name "OSC_8M_O2") (class "Default")
      (node (ref "C79") (pin "2") (pinfunction "2_2") (pintype "input"))
      (node (ref "U1") (pin "6") (pinfunction "PH1-OSC_OUT_6") (pintype "unspecified"))
      (node (ref "X3") (pin "2") (pinfunction "OSC2_2") (pintype "input"))
    )
    (net (code "83") (name "OSC_O1_STM") (class "Default")
      (node (ref "U1") (pin "3") (pinfunction "PC14-OSC32_IN_3") (pintype "unspecified"))
    )
    (net (code "84") (name "OSC_O2_STM") (class "Default")
      (node (ref "U1") (pin "4") (pinfunction "PC15-OSC32_OUT_4") (pintype "unspecified"))
    )
    (net (code "85") (name "PA5") (class "Default")
      (node (ref "H2") (pin "1") (pinfunction "1_1") (pintype "input"))
      (node (ref "U1") (pin "21") (pinfunction "PA5_21") (pintype "unspecified"))
    )
    (net (code "86") (name "PB6") (class "Default")
      (node (ref "H2") (pin "3") (pinfunction "3_3") (pintype "input"))
      (node (ref "U1") (pin "58") (pinfunction "PB6_58") (pintype "unspecified"))
    )
    (net (code "87") (name "PB10") (class "Default")
      (node (ref "H2") (pin "4") (pinfunction "4_4") (pintype "input"))
      (node (ref "U1") (pin "29") (pinfunction "PB10_29") (pintype "unspecified"))
    )
    (net (code "88") (name "PB12") (class "Default")
      (node (ref "H3") (pin "1") (pinfunction "1_1") (pintype "input"))
      (node (ref "U1") (pin "33") (pinfunction "PB12_33") (pintype "unspecified"))
    )
    (net (code "89") (name "PB13") (class "Default")
      (node (ref "H3") (pin "2") (pinfunction "2_2") (pintype "input"))
      (node (ref "U1") (pin "34") (pinfunction "PB13_34") (pintype "unspecified"))
    )
    (net (code "90") (name "PB14") (class "Default")
      (node (ref "H3") (pin "3") (pinfunction "3_3") (pintype "input"))
      (node (ref "U1") (pin "35") (pinfunction "PB14_35") (pintype "unspecified"))
    )
    (net (code "91") (name "PB15") (class "Default")
      (node (ref "H3") (pin "4") (pinfunction "4_4") (pintype "input"))
      (node (ref "U1") (pin "36") (pinfunction "PB15_36") (pintype "unspecified"))
    )
    (net (code "92") (name "PC12") (class "Default")
      (node (ref "H2") (pin "2") (pinfunction "2_2") (pintype "input"))
      (node (ref "U1") (pin "53") (pinfunction "PC12_53") (pintype "unspecified"))
    )
    (net (code "93") (name "STLINK_JTDI") (class "Default")
      (node (ref "P3") (pin "3") (pinfunction "3_3") (pintype "input"))
      (node (ref "U1") (pin "50") (pinfunction "PA15_50") (pintype "unspecified"))
    )
    (net (code "94") (name "STLINK_NJTRST") (class "Default")
      (node (ref "P3") (pin "5") (pinfunction "5_5") (pintype "input"))
      (node (ref "U1") (pin "56") (pinfunction "PB4_56") (pintype "unspecified"))
    )
    (net (code "95") (name "STLINK_NRST") (class "Default")
      (node (ref "C66") (pin "2") (pinfunction "2_2") (pintype "input"))
      (node (ref "H1") (pin "4") (pinfunction "4_4") (pintype "input"))
      (node (ref "R52") (pin "1") (pinfunction "1_1") (pintype "input"))
      (node (ref "R76") (pin "1") (pinfunction "1_1") (pintype "input"))
      (node (ref "U1") (pin "7") (pinfunction "NRST_7") (pintype "unspecified"))
    )
    (net (code "96") (name "STLINK_RX") (class "Default")
      (node (ref "H1") (pin "3") (pinfunction "3_3") (pintype "input"))
      (node (ref "U1") (pin "17") (pinfunction "PA3_17") (pintype "unspecified"))
    )
    (net (code "97") (name "STLINK_SWO") (class "Default")
      (node (ref "P3") (pin "4") (pinfunction "4_4") (pintype "input"))
      (node (ref "U1") (pin "55") (pinfunction "PB3_55") (pintype "unspecified"))
    )
    (net (code "98") (name "STLINK_TCK") (class "Default")
      (node (ref "P3") (pin "2") (pinfunction "2_2") (pintype "input"))
      (node (ref "U1") (pin "49") (pinfunction "PA14_49") (pintype "unspecified"))
    )
    (net (code "99") (name "STLINK_TMS") (class "Default")
      (node (ref "P3") (pin "1") (pinfunction "1_1") (pintype "input"))
      (node (ref "U1") (pin "46") (pinfunction "PA13_46") (pintype "unspecified"))
    )
    (net (code "100") (name "STLINK_TX") (class "Default")
      (node (ref "H1") (pin "2") (pinfunction "2_2") (pintype "input"))
      (node (ref "U1") (pin "16") (pinfunction "PA2_16") (pintype "unspecified"))
    )
    (net (code "101") (name "ST_LED1") (class "Default")
      (node (ref "R46") (pin "2") (pinfunction "2_2") (pintype "input"))
      (node (ref "U1") (pin "44") (pinfunction "PA11_44") (pintype "unspecified"))
    )
    (net (code "102") (name "ST_LED2") (class "Default")
      (node (ref "R47") (pin "2") (pinfunction "2_2") (pintype "input"))
      (node (ref "U1") (pin "45") (pinfunction "PA12_45") (pintype "unspecified"))
    )
    (net (code "103") (name "ST_LED3") (class "Default")
      (node (ref "R48") (pin "2") (pinfunction "2_2") (pintype "input"))
      (node (ref "U1") (pin "54") (pinfunction "PD2_54") (pintype "unspecified"))
    )
    (net (code "104") (name "UART_RX") (class "Default")
      (node (ref "U1") (pin "38") (pinfunction "PC7_38") (pintype "unspecified"))
      (node (ref "U11") (pin "1") (pinfunction "1_1") (pintype "unspecified"))
    )
    (net (code "105") (name "UART_TX") (class "Default")
      (node (ref "U1") (pin "37") (pinfunction "PC6_37") (pintype "unspecified"))
      (node (ref "U11") (pin "2") (pinfunction "2_2") (pintype "unspecified"))
    )
    (net (code "106") (name "unconnected-(SW1-Pad3)") (class "Default")
      (node (ref "SW1") (pin "3") (pinfunction "3_3") (pintype "input+no_connect"))
    )
    (net (code "107") (name "unconnected-(SW1-Pad4)") (class "Default")
      (node (ref "SW1") (pin "4") (pinfunction "4_4") (pintype "input+no_connect"))
    )
    (net (code "108") (name "unconnected-(SW1-Pad5)") (class "Default")
      (node (ref "SW1") (pin "5") (pinfunction "5_5") (pintype "input+no_connect"))
    )
    (net (code "109") (name "unconnected-(SW1-Pad6)") (class "Default")
      (node (ref "SW1") (pin "6") (pinfunction "6_6") (pintype "input+no_connect"))
    )
    (net (code "110") (name "unconnected-(SW2-Pad1)") (class "Default")
      (node (ref "SW2") (pin "1") (pinfunction "1_1") (pintype "input+no_connect"))
    )
    (net (code "111") (name "unconnected-(SW2-Pad4)") (class "Default")
      (node (ref "SW2") (pin "4") (pinfunction "4_4") (pintype "input+no_connect"))
    )
    (net (code "112") (name "unconnected-(SW3-Pad1)") (class "Default")
      (node (ref "SW3") (pin "1") (pinfunction "1_1") (pintype "input+no_connect"))
    )
    (net (code "113") (name "unconnected-(SW3-Pad4)") (class "Default")
      (node (ref "SW3") (pin "4") (pinfunction "4_4") (pintype "input+no_connect"))
    )
    (net (code "114") (name "unconnected-(SW4-Pad1)") (class "Default")
      (node (ref "SW4") (pin "1") (pinfunction "1_1") (pintype "input+no_connect"))
    )
    (net (code "115") (name "unconnected-(SW4-Pad4)") (class "Default")
      (node (ref "SW4") (pin "4") (pinfunction "4_4") (pintype "input+no_connect"))
    )
    (net (code "116") (name "unconnected-(U6-NC-Pad5)") (class "Default")
      (node (ref "U6") (pin "5") (pinfunction "NC_5") (pintype "unspecified+no_connect"))
    )
    (net (code "117") (name "unconnected-(U6-PG-Pad3)") (class "Default")
      (node (ref "U6") (pin "3") (pinfunction "PG_3") (pintype "unspecified+no_connect"))
    )
    (net (code "118") (name "unconnected-(USB1-DN1-Pad7)") (class "Default")
      (node (ref "USB1") (pin "7") (pinfunction "DN1_7") (pintype "unspecified+no_connect"))
    )
    (net (code "119") (name "unconnected-(USB1-DN2-Pad5)") (class "Default")
      (node (ref "USB1") (pin "5") (pinfunction "DN2_5") (pintype "unspecified+no_connect"))
    )
    (net (code "120") (name "unconnected-(USB1-DP1-Pad6)") (class "Default")
      (node (ref "USB1") (pin "6") (pinfunction "DP1_6") (pintype "unspecified+no_connect"))
    )
    (net (code "121") (name "unconnected-(USB1-DP2-Pad8)") (class "Default")
      (node (ref "USB1") (pin "8") (pinfunction "DP2_8") (pintype "unspecified+no_connect"))
    )
    (net (code "122") (name "unconnected-(USB1-SBU1-Pad9)") (class "Default")
      (node (ref "USB1") (pin "9") (pinfunction "SBU1_9") (pintype "unspecified+no_connect"))
    )
    (net (code "123") (name "unconnected-(USB1-SBU2-Pad3)") (class "Default")
      (node (ref "USB1") (pin "3") (pinfunction "SBU2_3") (pintype "unspecified+no_connect"))
    )
  )
)
